# 1.net
KiCad netlist of a schematic drawn in Altium Designer
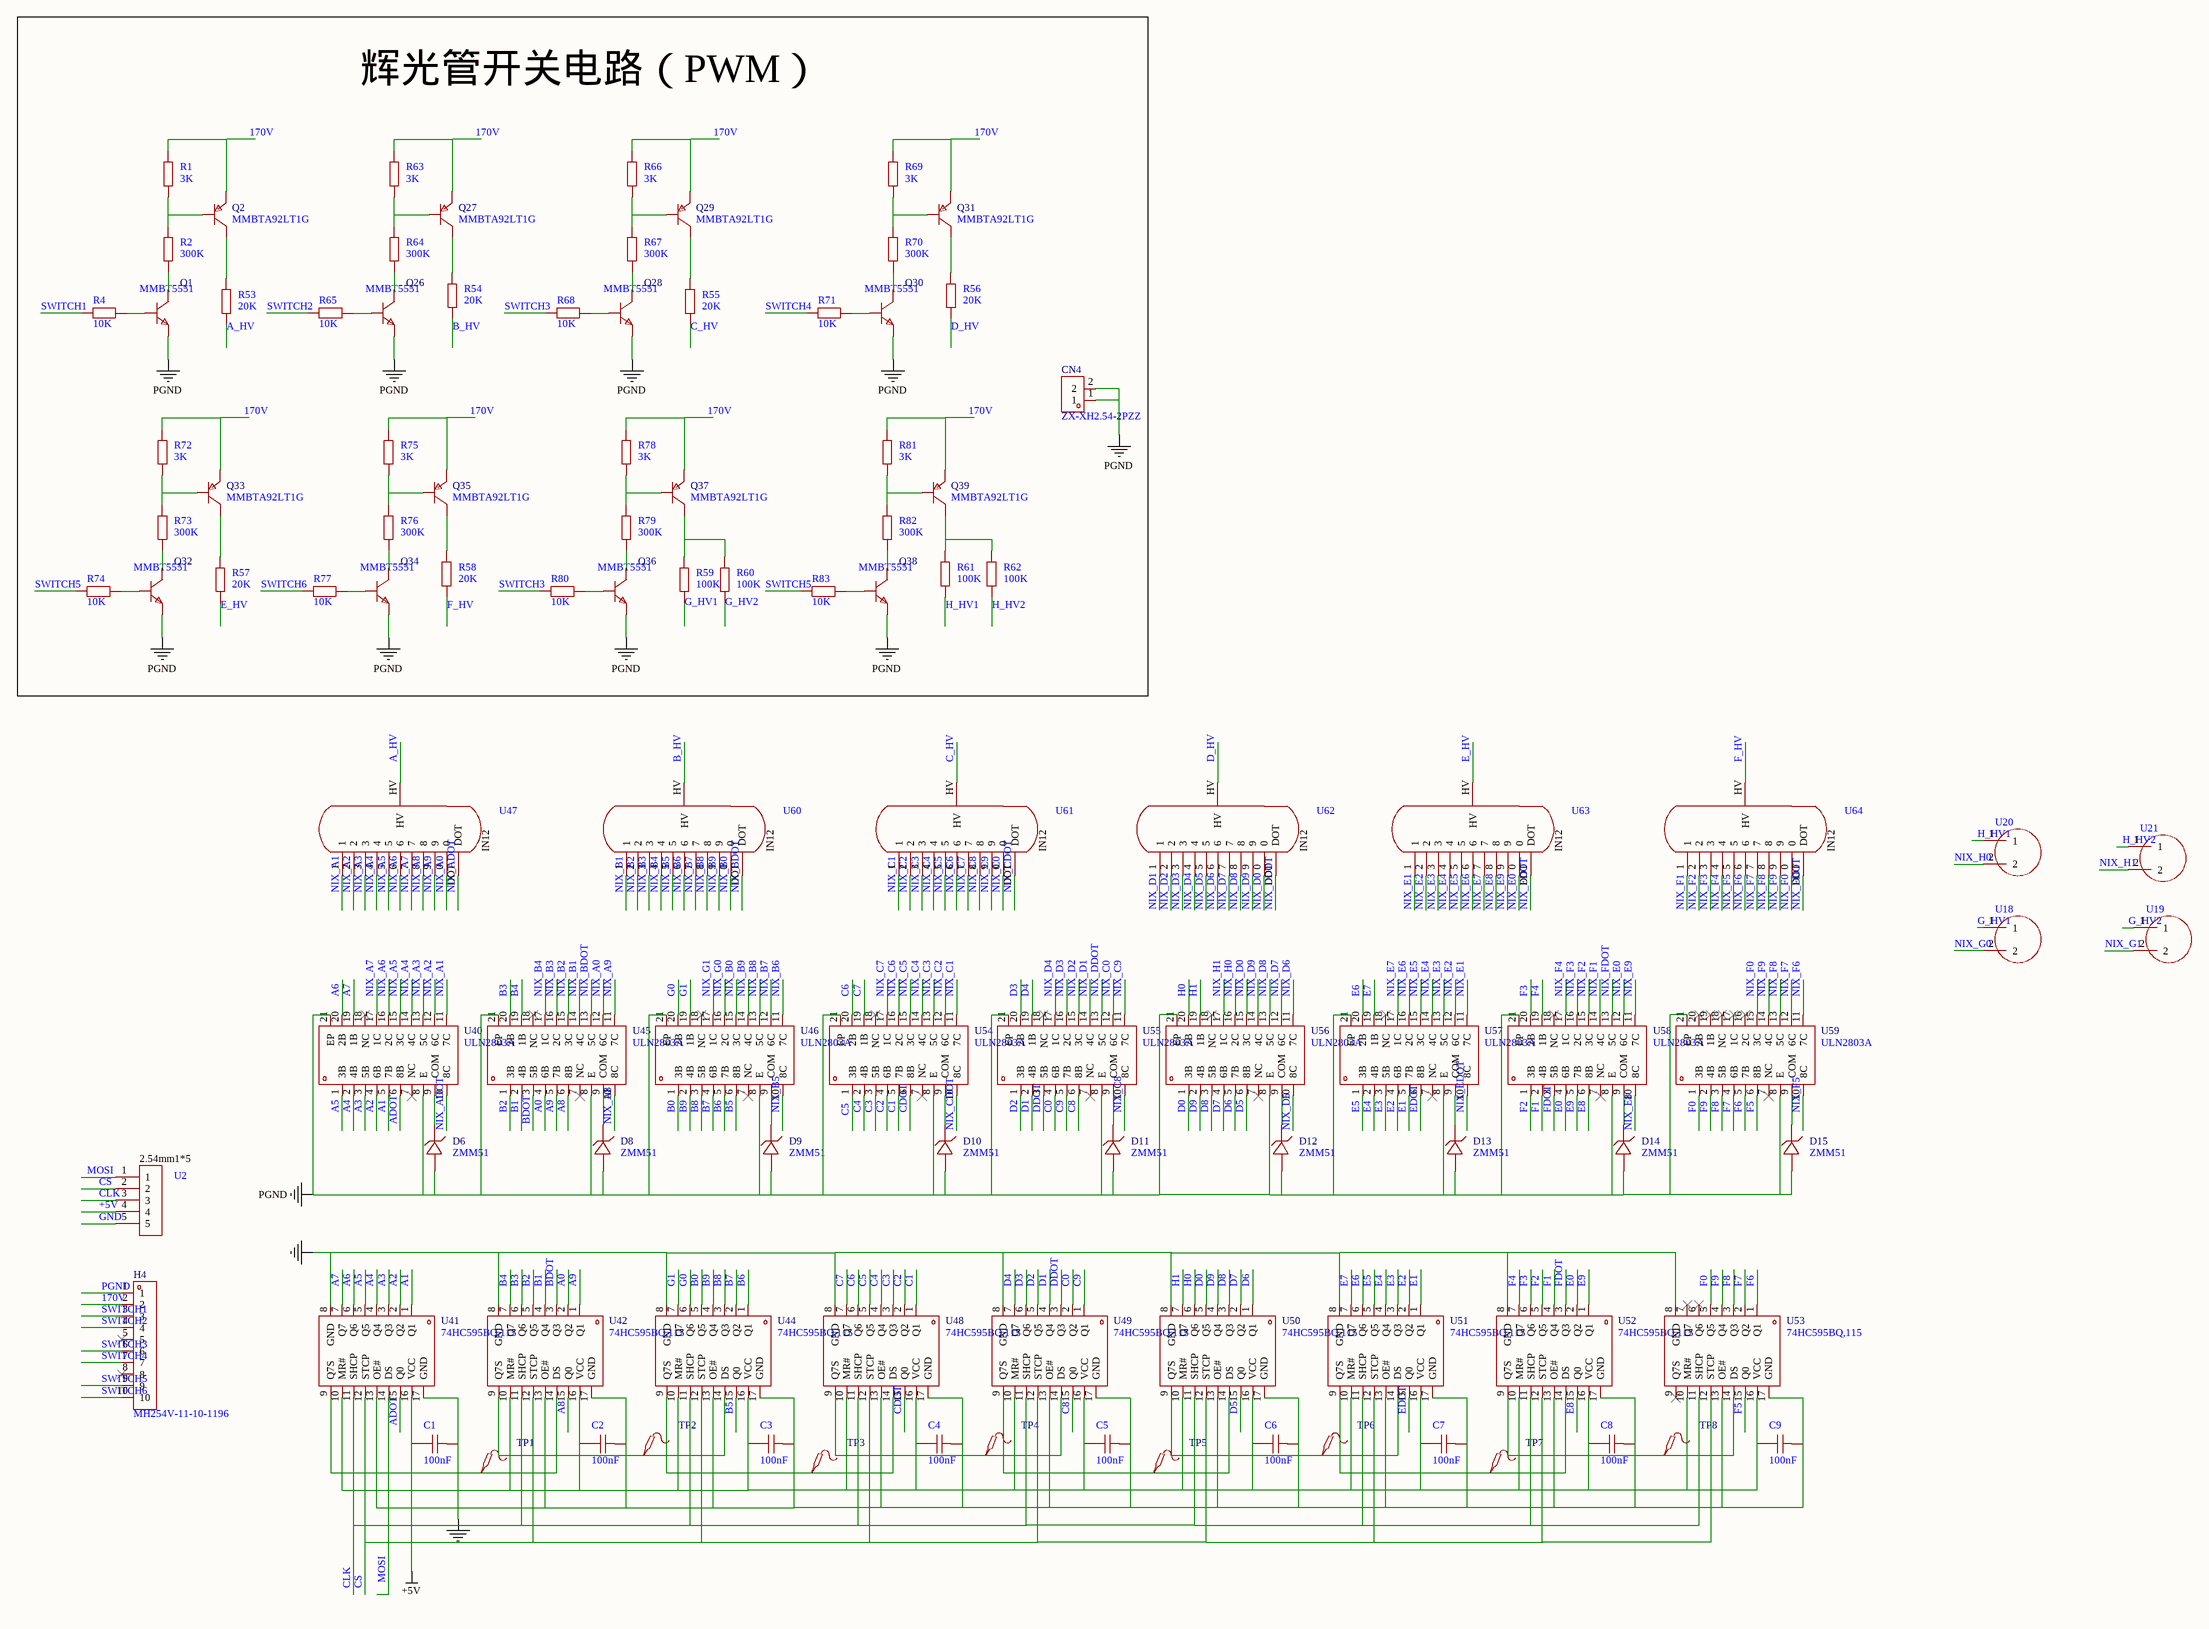
[diagram p0: 1_驱动.schdoc]

(export (version "E")
  (design (tool "Eeschema 10.0.6"))
  (components
    (comp (ref "C1")
      (value "100nF")
      (footprint "C0603")
      (libsource (lib "altium-import") (part "root_0_CAP_0603_"))
    )
    (comp (ref "C2")
      (value "100nF")
      (footprint "C0603")
      (libsource (lib "altium-import") (part "root_0_CAP_0603_"))
    )
    (comp (ref "C3")
      (value "100nF")
      (footprint "C0603")
      (libsource (lib "altium-import") (part "root_0_CAP_0603_"))
    )
    (comp (ref "C4")
      (value "100nF")
      (footprint "C0603")
      (libsource (lib "altium-import") (part "root_0_CAP_0603_"))
    )
    (comp (ref "C5")
      (value "100nF")
      (footprint "C0603")
      (libsource (lib "altium-import") (part "root_0_CAP_0603_"))
    )
    (comp (ref "C6")
      (value "100nF")
      (footprint "C0603")
      (libsource (lib "altium-import") (part "root_0_CAP_0603_"))
    )
    (comp (ref "C7")
      (value "100nF")
      (footprint "C0603")
      (libsource (lib "altium-import") (part "root_0_CAP_0603_"))
    )
    (comp (ref "C8")
      (value "100nF")
      (footprint "C0603")
      (libsource (lib "altium-import") (part "root_0_CAP_0603_"))
    )
    (comp (ref "C9")
      (value "100nF")
      (footprint "C0603")
      (libsource (lib "altium-import") (part "root_0_CAP_0603_"))
    )
    (comp (ref "CN4")
      (value "ZX-XH2.54-2PZZ")
      (footprint "CONN-TH_2P-P2.50_HX25003-2A")
      (fields (field (name "MANUFACTURER") "Megastar(兆星)"))
      (libsource (lib "altium-import") (part "root_2_ZX-XH2.54-2PZZ_"))
    )
    (comp (ref "D6")
      (value "ZMM51")
      (footprint "LL-34_L3.5-W1.5-RD")
      (fields (field (name "MANUFACTURER") "ST(先科)"))
      (libsource (lib "altium-import") (part "root_3_ZMM51_"))
    )
    (comp (ref "D8")
      (value "ZMM51")
      (footprint "LL-34_L3.5-W1.5-RD")
      (fields (field (name "MANUFACTURER") "ST(先科)"))
      (libsource (lib "altium-import") (part "root_3_ZMM51_"))
    )
    (comp (ref "D9")
      (value "ZMM51")
      (footprint "LL-34_L3.5-W1.5-RD")
      (fields (field (name "MANUFACTURER") "ST(先科)"))
      (libsource (lib "altium-import") (part "root_3_ZMM51_"))
    )
    (comp (ref "D10")
      (value "ZMM51")
      (footprint "LL-34_L3.5-W1.5-RD")
      (fields (field (name "MANUFACTURER") "ST(先科)"))
      (libsource (lib "altium-import") (part "root_3_ZMM51_"))
    )
    (comp (ref "D11")
      (value "ZMM51")
      (footprint "LL-34_L3.5-W1.5-RD")
      (fields (field (name "MANUFACTURER") "ST(先科)"))
      (libsource (lib "altium-import") (part "root_3_ZMM51_"))
    )
    (comp (ref "D12")
      (value "ZMM51")
      (footprint "LL-34_L3.5-W1.5-RD")
      (fields (field (name "MANUFACTURER") "ST(先科)"))
      (libsource (lib "altium-import") (part "root_3_ZMM51_"))
    )
    (comp (ref "D13")
      (value "ZMM51")
      (footprint "LL-34_L3.5-W1.5-RD")
      (fields (field (name "MANUFACTURER") "ST(先科)"))
      (libsource (lib "altium-import") (part "root_3_ZMM51_"))
    )
    (comp (ref "D14")
      (value "ZMM51")
      (footprint "LL-34_L3.5-W1.5-RD")
      (fields (field (name "MANUFACTURER") "ST(先科)"))
      (libsource (lib "altium-import") (part "root_3_ZMM51_"))
    )
    (comp (ref "D15")
      (value "ZMM51")
      (footprint "LL-34_L3.5-W1.5-RD")
      (fields (field (name "MANUFACTURER") "ST(先科)"))
      (libsource (lib "altium-import") (part "root_3_ZMM51_"))
    )
    (comp (ref "H4")
      (value "MH254V-11-10-1196")
      (footprint "HDR-TH_10P-P2.54-V-M")
      (fields (field (name "MANUFACTURER") "XFCN(兴飞)"))
      (libsource (lib "altium-import") (part "root_0_MH254V-11-10-1196_"))
    )
    (comp (ref "Q1")
      (value "MMBT5551")
      (footprint "SOT-23-3_L2.9-W1.3-P1.90-LS2.4-BR")
      (fields (field (name "MANUFACTURER") "CJ(江苏长电/长晶)"))
      (libsource (lib "altium-import") (part "root_0_MMBT5551_C2145_"))
    )
    (comp (ref "Q2")
      (value "MMBTA92LT1G")
      (footprint "SOT-23-3_L2.9-W1.6-P1.90-LS2.8-BR")
      (fields (field (name "MANUFACTURER") "onsemi(安森美)"))
      (libsource (lib "altium-import") (part "root_2_mirrored_MMBTA92LT1G_"))
    )
    (comp (ref "Q26")
      (value "MMBT5551")
      (footprint "SOT-23-3_L2.9-W1.3-P1.90-LS2.4-BR")
      (fields (field (name "MANUFACTURER") "CJ(江苏长电/长晶)"))
      (libsource (lib "altium-import") (part "root_0_MMBT5551_C2145_"))
    )
    (comp (ref "Q27")
      (value "MMBTA92LT1G")
      (footprint "SOT-23-3_L2.9-W1.6-P1.90-LS2.8-BR")
      (fields (field (name "MANUFACTURER") "onsemi(安森美)"))
      (libsource (lib "altium-import") (part "root_2_mirrored_MMBTA92LT1G_"))
    )
    (comp (ref "Q28")
      (value "MMBT5551")
      (footprint "SOT-23-3_L2.9-W1.3-P1.90-LS2.4-BR")
      (fields (field (name "MANUFACTURER") "CJ(江苏长电/长晶)"))
      (libsource (lib "altium-import") (part "root_0_MMBT5551_C2145_"))
    )
    (comp (ref "Q29")
      (value "MMBTA92LT1G")
      (footprint "SOT-23-3_L2.9-W1.6-P1.90-LS2.8-BR")
      (fields (field (name "MANUFACTURER") "onsemi(安森美)"))
      (libsource (lib "altium-import") (part "root_2_mirrored_MMBTA92LT1G_"))
    )
    (comp (ref "Q30")
      (value "MMBT5551")
      (footprint "SOT-23-3_L2.9-W1.3-P1.90-LS2.4-BR")
      (fields (field (name "MANUFACTURER") "CJ(江苏长电/长晶)"))
      (libsource (lib "altium-import") (part "root_0_MMBT5551_C2145_"))
    )
    (comp (ref "Q31")
      (value "MMBTA92LT1G")
      (footprint "SOT-23-3_L2.9-W1.6-P1.90-LS2.8-BR")
      (fields (field (name "MANUFACTURER") "onsemi(安森美)"))
      (libsource (lib "altium-import") (part "root_2_mirrored_MMBTA92LT1G_"))
    )
    (comp (ref "Q32")
      (value "MMBT5551")
      (footprint "SOT-23-3_L2.9-W1.3-P1.90-LS2.4-BR")
      (fields (field (name "MANUFACTURER") "CJ(江苏长电/长晶)"))
      (libsource (lib "altium-import") (part "root_0_MMBT5551_C2145_"))
    )
    (comp (ref "Q33")
      (value "MMBTA92LT1G")
      (footprint "SOT-23-3_L2.9-W1.6-P1.90-LS2.8-BR")
      (fields (field (name "MANUFACTURER") "onsemi(安森美)"))
      (libsource (lib "altium-import") (part "root_2_mirrored_MMBTA92LT1G_"))
    )
    (comp (ref "Q34")
      (value "MMBT5551")
      (footprint "SOT-23-3_L2.9-W1.3-P1.90-LS2.4-BR")
      (fields (field (name "MANUFACTURER") "CJ(江苏长电/长晶)"))
      (libsource (lib "altium-import") (part "root_0_MMBT5551_C2145_"))
    )
    (comp (ref "Q35")
      (value "MMBTA92LT1G")
      (footprint "SOT-23-3_L2.9-W1.6-P1.90-LS2.8-BR")
      (fields (field (name "MANUFACTURER") "onsemi(安森美)"))
      (libsource (lib "altium-import") (part "root_2_mirrored_MMBTA92LT1G_"))
    )
    (comp (ref "Q36")
      (value "MMBT5551")
      (footprint "SOT-23-3_L2.9-W1.3-P1.90-LS2.4-BR")
      (fields (field (name "MANUFACTURER") "CJ(江苏长电/长晶)"))
      (libsource (lib "altium-import") (part "root_0_MMBT5551_C2145_"))
    )
    (comp (ref "Q37")
      (value "MMBTA92LT1G")
      (footprint "SOT-23-3_L2.9-W1.6-P1.90-LS2.8-BR")
      (fields (field (name "MANUFACTURER") "onsemi(安森美)"))
      (libsource (lib "altium-import") (part "root_2_mirrored_MMBTA92LT1G_"))
    )
    (comp (ref "Q38")
      (value "MMBT5551")
      (footprint "SOT-23-3_L2.9-W1.3-P1.90-LS2.4-BR")
      (fields (field (name "MANUFACTURER") "CJ(江苏长电/长晶)"))
      (libsource (lib "altium-import") (part "root_0_MMBT5551_C2145_"))
    )
    (comp (ref "Q39")
      (value "MMBTA92LT1G")
      (footprint "SOT-23-3_L2.9-W1.6-P1.90-LS2.8-BR")
      (fields (field (name "MANUFACTURER") "onsemi(安森美)"))
      (libsource (lib "altium-import") (part "root_2_mirrored_MMBTA92LT1G_"))
    )
    (comp (ref "R1")
      (value "3K")
      (footprint "R0603")
      (libsource (lib "altium-import") (part "root_1_Res_0603_"))
    )
    (comp (ref "R2")
      (value "300K")
      (footprint "R0603")
      (libsource (lib "altium-import") (part "root_1_Res_0603_"))
    )
    (comp (ref "R4")
      (value "10K")
      (footprint "R0603")
      (libsource (lib "altium-import") (part "root_0_Res_0603_"))
    )
    (comp (ref "R53")
      (value "20K")
      (footprint "R0603")
      (libsource (lib "altium-import") (part "root_1_Res_0603_"))
    )
    (comp (ref "R54")
      (value "20K")
      (footprint "R0603")
      (libsource (lib "altium-import") (part "root_1_Res_0603_"))
    )
    (comp (ref "R55")
      (value "20K")
      (footprint "R0603")
      (libsource (lib "altium-import") (part "root_1_Res_0603_"))
    )
    (comp (ref "R56")
      (value "20K")
      (footprint "R0603")
      (libsource (lib "altium-import") (part "root_1_Res_0603_"))
    )
    (comp (ref "R57")
      (value "20K")
      (footprint "R0603")
      (libsource (lib "altium-import") (part "root_1_Res_0603_"))
    )
    (comp (ref "R58")
      (value "20K")
      (footprint "R0603")
      (libsource (lib "altium-import") (part "root_1_Res_0603_"))
    )
    (comp (ref "R59")
      (value "100K")
      (footprint "R0603")
      (libsource (lib "altium-import") (part "root_1_Res_0603_"))
    )
    (comp (ref "R60")
      (value "100K")
      (footprint "R0603")
      (libsource (lib "altium-import") (part "root_1_Res_0603_"))
    )
    (comp (ref "R61")
      (value "100K")
      (footprint "R0603")
      (libsource (lib "altium-import") (part "root_1_Res_0603_"))
    )
    (comp (ref "R62")
      (value "100K")
      (footprint "R0603")
      (libsource (lib "altium-import") (part "root_1_Res_0603_"))
    )
    (comp (ref "R63")
      (value "3K")
      (footprint "R0603")
      (libsource (lib "altium-import") (part "root_1_Res_0603_"))
    )
    (comp (ref "R64")
      (value "300K")
      (footprint "R0603")
      (libsource (lib "altium-import") (part "root_1_Res_0603_"))
    )
    (comp (ref "R65")
      (value "10K")
      (footprint "R0603")
      (libsource (lib "altium-import") (part "root_0_Res_0603_"))
    )
    (comp (ref "R66")
      (value "3K")
      (footprint "R0603")
      (libsource (lib "altium-import") (part "root_1_Res_0603_"))
    )
    (comp (ref "R67")
      (value "300K")
      (footprint "R0603")
      (libsource (lib "altium-import") (part "root_1_Res_0603_"))
    )
    (comp (ref "R68")
      (value "10K")
      (footprint "R0603")
      (libsource (lib "altium-import") (part "root_0_Res_0603_"))
    )
    (comp (ref "R69")
      (value "3K")
      (footprint "R0603")
      (libsource (lib "altium-import") (part "root_1_Res_0603_"))
    )
    (comp (ref "R70")
      (value "300K")
      (footprint "R0603")
      (libsource (lib "altium-import") (part "root_1_Res_0603_"))
    )
    (comp (ref "R71")
      (value "10K")
      (footprint "R0603")
      (libsource (lib "altium-import") (part "root_0_Res_0603_"))
    )
    (comp (ref "R72")
      (value "3K")
      (footprint "R0603")
      (libsource (lib "altium-import") (part "root_1_Res_0603_"))
    )
    (comp (ref "R73")
      (value "300K")
      (footprint "R0603")
      (libsource (lib "altium-import") (part "root_1_Res_0603_"))
    )
    (comp (ref "R74")
      (value "10K")
      (footprint "R0603")
      (libsource (lib "altium-import") (part "root_0_Res_0603_"))
    )
    (comp (ref "R75")
      (value "3K")
      (footprint "R0603")
      (libsource (lib "altium-import") (part "root_1_Res_0603_"))
    )
    (comp (ref "R76")
      (value "300K")
      (footprint "R0603")
      (libsource (lib "altium-import") (part "root_1_Res_0603_"))
    )
    (comp (ref "R77")
      (value "10K")
      (footprint "R0603")
      (libsource (lib "altium-import") (part "root_0_Res_0603_"))
    )
    (comp (ref "R78")
      (value "3K")
      (footprint "R0603")
      (libsource (lib "altium-import") (part "root_1_Res_0603_"))
    )
    (comp (ref "R79")
      (value "300K")
      (footprint "R0603")
      (libsource (lib "altium-import") (part "root_1_Res_0603_"))
    )
    (comp (ref "R80")
      (value "10K")
      (footprint "R0603")
      (libsource (lib "altium-import") (part "root_0_Res_0603_"))
    )
    (comp (ref "R81")
      (value "3K")
      (footprint "R0603")
      (libsource (lib "altium-import") (part "root_1_Res_0603_"))
    )
    (comp (ref "R82")
      (value "300K")
      (footprint "R0603")
      (libsource (lib "altium-import") (part "root_1_Res_0603_"))
    )
    (comp (ref "R83")
      (value "10K")
      (footprint "R0603")
      (libsource (lib "altium-import") (part "root_0_Res_0603_"))
    )
    (comp (ref "TP1")
      (value "~")
      (footprint "Test-Point-0.5mm")
      (libsource (lib "altium-import") (part "root_0_Test-Point_"))
    )
    (comp (ref "TP2")
      (value "~")
      (footprint "Test-Point-0.5mm")
      (libsource (lib "altium-import") (part "root_0_Test-Point_"))
    )
    (comp (ref "TP3")
      (value "~")
      (footprint "Test-Point-0.5mm")
      (libsource (lib "altium-import") (part "root_0_Test-Point_"))
    )
    (comp (ref "TP4")
      (value "~")
      (footprint "Test-Point-0.5mm")
      (libsource (lib "altium-import") (part "root_0_Test-Point_"))
    )
    (comp (ref "TP5")
      (value "~")
      (footprint "Test-Point-0.5mm")
      (libsource (lib "altium-import") (part "root_0_Test-Point_"))
    )
    (comp (ref "TP6")
      (value "~")
      (footprint "Test-Point-0.5mm")
      (libsource (lib "altium-import") (part "root_0_Test-Point_"))
    )
    (comp (ref "TP7")
      (value "~")
      (footprint "Test-Point-0.5mm")
      (libsource (lib "altium-import") (part "root_0_Test-Point_"))
    )
    (comp (ref "TP8")
      (value "~")
      (footprint "Test-Point-0.5mm")
      (libsource (lib "altium-import") (part "root_0_Test-Point_"))
    )
    (comp (ref "U2")
      (value "~")
      (footprint "2.54mm1*5")
      (libsource (lib "altium-import") (part "root_0_2.54mm1*5_"))
    )
    (comp (ref "U18") (value "~") (footprint "6*13氖泡") (libsource (lib "altium-import") (part "root_3_氖泡_")))
    (comp (ref "U19") (value "~") (footprint "6*13氖泡") (libsource (lib "altium-import") (part "root_3_氖泡_")))
    (comp (ref "U20") (value "~") (footprint "6*13氖泡") (libsource (lib "altium-import") (part "root_3_氖泡_")))
    (comp (ref "U21") (value "~") (footprint "6*13氖泡") (libsource (lib "altium-import") (part "root_3_氖泡_")))
    (comp (ref "U40")
      (value "ULN2803A")
      (footprint "QFN-20_L4.0-W4.0-P0.50-BL-EP")
      (fields (field (name "MANUFACTURER") "Mixic(中科芯亿达)"))
      (libsource (lib "altium-import") (part "root_1_ULN2803A_C493377_"))
    )
    (comp (ref "U41")
      (value "74HC595BQ,115")
      (footprint "DHVQFN-16_L3.5-W2.5-P0.50-BL-EP")
      (fields (field (name "MANUFACTURER") "Nexperia(安世)"))
      (libsource (lib "altium-import") (part "root_3_74HC595BQ,115_"))
    )
    (comp (ref "U42")
      (value "74HC595BQ,115")
      (footprint "DHVQFN-16_L3.5-W2.5-P0.50-BL-EP")
      (fields (field (name "MANUFACTURER") "Nexperia(安世)"))
      (libsource (lib "altium-import") (part "root_3_74HC595BQ,115_"))
    )
    (comp (ref "U44")
      (value "74HC595BQ,115")
      (footprint "DHVQFN-16_L3.5-W2.5-P0.50-BL-EP")
      (fields (field (name "MANUFACTURER") "Nexperia(安世)"))
      (libsource (lib "altium-import") (part "root_3_74HC595BQ,115_"))
    )
    (comp (ref "U45")
      (value "ULN2803A")
      (footprint "QFN-20_L4.0-W4.0-P0.50-BL-EP")
      (fields (field (name "MANUFACTURER") "Mixic(中科芯亿达)"))
      (libsource (lib "altium-import") (part "root_1_ULN2803A_C493377_"))
    )
    (comp (ref "U46")
      (value "ULN2803A")
      (footprint "QFN-20_L4.0-W4.0-P0.50-BL-EP")
      (fields (field (name "MANUFACTURER") "Mixic(中科芯亿达)"))
      (libsource (lib "altium-import") (part "root_1_ULN2803A_C493377_"))
    )
    (comp (ref "U47") (value "~") (footprint "IN12") (libsource (lib "altium-import") (part "root_1_IN12_")))
    (comp (ref "U48")
      (value "74HC595BQ,115")
      (footprint "DHVQFN-16_L3.5-W2.5-P0.50-BL-EP")
      (fields (field (name "MANUFACTURER") "Nexperia(安世)"))
      (libsource (lib "altium-import") (part "root_3_74HC595BQ,115_"))
    )
    (comp (ref "U49")
      (value "74HC595BQ,115")
      (footprint "DHVQFN-16_L3.5-W2.5-P0.50-BL-EP")
      (fields (field (name "MANUFACTURER") "Nexperia(安世)"))
      (libsource (lib "altium-import") (part "root_3_74HC595BQ,115_"))
    )
    (comp (ref "U50")
      (value "74HC595BQ,115")
      (footprint "DHVQFN-16_L3.5-W2.5-P0.50-BL-EP")
      (fields (field (name "MANUFACTURER") "Nexperia(安世)"))
      (libsource (lib "altium-import") (part "root_3_74HC595BQ,115_"))
    )
    (comp (ref "U51")
      (value "74HC595BQ,115")
      (footprint "DHVQFN-16_L3.5-W2.5-P0.50-BL-EP")
      (fields (field (name "MANUFACTURER") "Nexperia(安世)"))
      (libsource (lib "altium-import") (part "root_3_74HC595BQ,115_"))
    )
    (comp (ref "U52")
      (value "74HC595BQ,115")
      (footprint "DHVQFN-16_L3.5-W2.5-P0.50-BL-EP")
      (fields (field (name "MANUFACTURER") "Nexperia(安世)"))
      (libsource (lib "altium-import") (part "root_3_74HC595BQ,115_"))
    )
    (comp (ref "U53")
      (value "74HC595BQ,115")
      (footprint "DHVQFN-16_L3.5-W2.5-P0.50-BL-EP")
      (fields (field (name "MANUFACTURER") "Nexperia(安世)"))
      (libsource (lib "altium-import") (part "root_3_74HC595BQ,115_"))
    )
    (comp (ref "U54")
      (value "ULN2803A")
      (footprint "QFN-20_L4.0-W4.0-P0.50-BL-EP")
      (fields (field (name "MANUFACTURER") "Mixic(中科芯亿达)"))
      (libsource (lib "altium-import") (part "root_1_ULN2803A_C493377_"))
    )
    (comp (ref "U55")
      (value "ULN2803A")
      (footprint "QFN-20_L4.0-W4.0-P0.50-BL-EP")
      (fields (field (name "MANUFACTURER") "Mixic(中科芯亿达)"))
      (libsource (lib "altium-import") (part "root_1_ULN2803A_C493377_"))
    )
    (comp (ref "U56")
      (value "ULN2803A")
      (footprint "QFN-20_L4.0-W4.0-P0.50-BL-EP")
      (fields (field (name "MANUFACTURER") "Mixic(中科芯亿达)"))
      (libsource (lib "altium-import") (part "root_1_ULN2803A_C493377_"))
    )
    (comp (ref "U57")
      (value "ULN2803A")
      (footprint "QFN-20_L4.0-W4.0-P0.50-BL-EP")
      (fields (field (name "MANUFACTURER") "Mixic(中科芯亿达)"))
      (libsource (lib "altium-import") (part "root_1_ULN2803A_C493377_"))
    )
    (comp (ref "U58")
      (value "ULN2803A")
      (footprint "QFN-20_L4.0-W4.0-P0.50-BL-EP")
      (fields (field (name "MANUFACTURER") "Mixic(中科芯亿达)"))
      (libsource (lib "altium-import") (part "root_1_ULN2803A_C493377_"))
    )
    (comp (ref "U59")
      (value "ULN2803A")
      (footprint "QFN-20_L4.0-W4.0-P0.50-BL-EP")
      (fields (field (name "MANUFACTURER") "Mixic(中科芯亿达)"))
      (libsource (lib "altium-import") (part "root_1_ULN2803A_C493377_"))
    )
    (comp (ref "U60") (value "~") (footprint "IN12") (libsource (lib "altium-import") (part "root_1_IN12_")))
    (comp (ref "U61") (value "~") (footprint "IN12") (libsource (lib "altium-import") (part "root_1_IN12_")))
    (comp (ref "U62") (value "~") (footprint "IN12") (libsource (lib "altium-import") (part "root_1_IN12_")))
    (comp (ref "U63") (value "~") (footprint "IN12") (libsource (lib "altium-import") (part "root_1_IN12_")))
    (comp (ref "U64") (value "~") (footprint "IN12") (libsource (lib "altium-import") (part "root_1_IN12_")))
  )
  (nets
    (net (code "1") (name "+5V") (class "Default")
      (node (ref "C1") (pin "1") (pinfunction "1_1") (pintype "passive"))
      (node (ref "C2") (pin "1") (pinfunction "1_1") (pintype "passive"))
      (node (ref "C3") (pin "1") (pinfunction "1_1") (pintype "passive"))
      (node (ref "C4") (pin "1") (pinfunction "1_1") (pintype "passive"))
      (node (ref "C5") (pin "1") (pinfunction "1_1") (pintype "passive"))
      (node (ref "C6") (pin "1") (pinfunction "1_1") (pintype "passive"))
      (node (ref "C7") (pin "1") (pinfunction "1_1") (pintype "passive"))
      (node (ref "C8") (pin "1") (pinfunction "1_1") (pintype "passive"))
      (node (ref "C9") (pin "1") (pinfunction "1_1") (pintype "passive"))
      (node (ref "U2") (pin "4") (pinfunction "4_4") (pintype "passive"))
      (node (ref "U41") (pin "10") (pinfunction "MR#_10") (pintype "passive"))
      (node (ref "U41") (pin "16") (pinfunction "VCC_16") (pintype "passive"))
      (node (ref "U42") (pin "10") (pinfunction "MR#_10") (pintype "passive"))
      (node (ref "U42") (pin "16") (pinfunction "VCC_16") (pintype "passive"))
      (node (ref "U44") (pin "10") (pinfunction "MR#_10") (pintype "passive"))
      (node (ref "U44") (pin "16") (pinfunction "VCC_16") (pintype "passive"))
      (node (ref "U48") (pin "10") (pinfunction "MR#_10") (pintype "passive"))
      (node (ref "U48") (pin "16") (pinfunction "VCC_16") (pintype "passive"))
      (node (ref "U49") (pin "10") (pinfunction "MR#_10") (pintype "passive"))
      (node (ref "U49") (pin "16") (pinfunction "VCC_16") (pintype "passive"))
      (node (ref "U50") (pin "10") (pinfunction "MR#_10") (pintype "passive"))
      (node (ref "U50") (pin "16") (pinfunction "VCC_16") (pintype "passive"))
      (node (ref "U51") (pin "10") (pinfunction "MR#_10") (pintype "passive"))
      (node (ref "U51") (pin "16") (pinfunction "VCC_16") (pintype "passive"))
      (node (ref "U52") (pin "10") (pinfunction "MR#_10") (pintype "passive"))
      (node (ref "U52") (pin "16") (pinfunction "VCC_16") (pintype "passive"))
      (node (ref "U53") (pin "10") (pinfunction "MR#_10") (pintype "passive"))
      (node (ref "U53") (pin "16") (pinfunction "VCC_16") (pintype "passive"))
    )
    (net (code "2") (name "/170V") (class "Default")
      (node (ref "H4") (pin "2") (pinfunction "2_2") (pintype "passive"))
      (node (ref "Q2") (pin "2") (pinfunction "E_2") (pintype "passive"))
      (node (ref "Q27") (pin "2") (pinfunction "E_2") (pintype "passive"))
      (node (ref "Q29") (pin "2") (pinfunction "E_2") (pintype "passive"))
      (node (ref "Q31") (pin "2") (pinfunction "E_2") (pintype "passive"))
      (node (ref "Q33") (pin "2") (pinfunction "E_2") (pintype "passive"))
      (node (ref "Q35") (pin "2") (pinfunction "E_2") (pintype "passive"))
      (node (ref "Q37") (pin "2") (pinfunction "E_2") (pintype "passive"))
      (node (ref "Q39") (pin "2") (pinfunction "E_2") (pintype "passive"))
      (node (ref "R1") (pin "2") (pinfunction "2_2") (pintype "passive"))
      (node (ref "R63") (pin "2") (pinfunction "2_2") (pintype "passive"))
      (node (ref "R66") (pin "2") (pinfunction "2_2") (pintype "passive"))
      (node (ref "R69") (pin "2") (pinfunction "2_2") (pintype "passive"))
      (node (ref "R72") (pin "2") (pinfunction "2_2") (pintype "passive"))
      (node (ref "R75") (pin "2") (pinfunction "2_2") (pintype "passive"))
      (node (ref "R78") (pin "2") (pinfunction "2_2") (pintype "passive"))
      (node (ref "R81") (pin "2") (pinfunction "2_2") (pintype "passive"))
    )
    (net (code "3") (name "/A0") (class "Default")
      (node (ref "U42") (pin "2") (pinfunction "Q2_2") (pintype "passive"))
      (node (ref "U45") (pin "4") (pinfunction "6B_4") (pintype "passive"))
    )
    (net (code "4") (name "/A1") (class "Default")
      (node (ref "U40") (pin "5") (pinfunction "7B_5") (pintype "passive"))
      (node (ref "U41") (pin "1") (pinfunction "Q1_1") (pintype "passive"))
    )
    (net (code "5") (name "/A2") (class "Default")
      (node (ref "U40") (pin "4") (pinfunction "6B_4") (pintype "passive"))
      (node (ref "U41") (pin "2") (pinfunction "Q2_2") (pintype "passive"))
    )
    (net (code "6") (name "/A3") (class "Default")
      (node (ref "U40") (pin "3") (pinfunction "5B_3") (pintype "passive"))
      (node (ref "U41") (pin "3") (pinfunction "Q3_3") (pintype "passive"))
    )
    (net (code "7") (name "/A4") (class "Default")
      (node (ref "U40") (pin "2") (pinfunction "4B_2") (pintype "passive"))
      (node (ref "U41") (pin "4") (pinfunction "Q4_4") (pintype "passive"))
    )
    (net (code "8") (name "/A5") (class "Default")
      (node (ref "U40") (pin "1") (pinfunction "3B_1") (pintype "passive"))
      (node (ref "U41") (pin "5") (pinfunction "Q5_5") (pintype "passive"))
    )
    (net (code "9") (name "/A6") (class "Default")
      (node (ref "U40") (pin "20") (pinfunction "2B_20") (pintype "passive"))
      (node (ref "U41") (pin "6") (pinfunction "Q6_6") (pintype "passive"))
    )
    (net (code "10") (name "/A7") (class "Default")
      (node (ref "U40") (pin "19") (pinfunction "1B_19") (pintype "passive"))
      (node (ref "U41") (pin "7") (pinfunction "Q7_7") (pintype "passive"))
    )
    (net (code "11") (name "/A8") (class "Default")
      (node (ref "U42") (pin "15") (pinfunction "Q0_15") (pintype "passive"))
      (node (ref "U45") (pin "6") (pinfunction "8B_6") (pintype "passive"))
    )
    (net (code "12") (name "/A9") (class "Default")
      (node (ref "U42") (pin "1") (pinfunction "Q1_1") (pintype "passive"))
      (node (ref "U45") (pin "5") (pinfunction "7B_5") (pintype "passive"))
    )
    (net (code "13") (name "/ADOT") (class "Default")
      (node (ref "U40") (pin "6") (pinfunction "8B_6") (pintype "passive"))
      (node (ref "U41") (pin "15") (pinfunction "Q0_15") (pintype "passive"))
    )
    (net (code "14") (name "/A_HV") (class "Default")
      (node (ref "R53") (pin "1") (pinfunction "1_1") (pintype "passive"))
      (node (ref "U47") (pin "HV") (pinfunction "HV_HV") (pintype "passive"))
    )
    (net (code "15") (name "/B0") (class "Default")
      (node (ref "U44") (pin "5") (pinfunction "Q5_5") (pintype "passive"))
      (node (ref "U46") (pin "1") (pinfunction "3B_1") (pintype "passive"))
    )
    (net (code "16") (name "/B1") (class "Default")
      (node (ref "U42") (pin "4") (pinfunction "Q4_4") (pintype "passive"))
      (node (ref "U45") (pin "2") (pinfunction "4B_2") (pintype "passive"))
    )
    (net (code "17") (name "/B2") (class "Default")
      (node (ref "U42") (pin "5") (pinfunction "Q5_5") (pintype "passive"))
      (node (ref "U45") (pin "1") (pinfunction "3B_1") (pintype "passive"))
    )
    (net (code "18") (name "/B3") (class "Default")
      (node (ref "U42") (pin "6") (pinfunction "Q6_6") (pintype "passive"))
      (node (ref "U45") (pin "20") (pinfunction "2B_20") (pintype "passive"))
    )
    (net (code "19") (name "/B4") (class "Default")
      (node (ref "U42") (pin "7") (pinfunction "Q7_7") (pintype "passive"))
      (node (ref "U45") (pin "19") (pinfunction "1B_19") (pintype "passive"))
    )
    (net (code "20") (name "/B5") (class "Default")
      (node (ref "U44") (pin "15") (pinfunction "Q0_15") (pintype "passive"))
      (node (ref "U46") (pin "6") (pinfunction "8B_6") (pintype "passive"))
    )
    (net (code "21") (name "/B6") (class "Default")
      (node (ref "U44") (pin "1") (pinfunction "Q1_1") (pintype "passive"))
      (node (ref "U46") (pin "5") (pinfunction "7B_5") (pintype "passive"))
    )
    (net (code "22") (name "/B7") (class "Default")
      (node (ref "U44") (pin "2") (pinfunction "Q2_2") (pintype "passive"))
      (node (ref "U46") (pin "4") (pinfunction "6B_4") (pintype "passive"))
    )
    (net (code "23") (name "/B8") (class "Default")
      (node (ref "U44") (pin "3") (pinfunction "Q3_3") (pintype "passive"))
      (node (ref "U46") (pin "3") (pinfunction "5B_3") (pintype "passive"))
    )
    (net (code "24") (name "/B9") (class "Default")
      (node (ref "U44") (pin "4") (pinfunction "Q4_4") (pintype "passive"))
      (node (ref "U46") (pin "2") (pinfunction "4B_2") (pintype "passive"))
    )
    (net (code "25") (name "/BDOT") (class "Default")
      (node (ref "U42") (pin "3") (pinfunction "Q3_3") (pintype "passive"))
      (node (ref "U45") (pin "3") (pinfunction "5B_3") (pintype "passive"))
    )
    (net (code "26") (name "/B_HV") (class "Default")
      (node (ref "R54") (pin "1") (pinfunction "1_1") (pintype "passive"))
      (node (ref "U60") (pin "HV") (pinfunction "HV_HV") (pintype "passive"))
    )
    (net (code "27") (name "/C0") (class "Default")
      (node (ref "U49") (pin "2") (pinfunction "Q2_2") (pintype "passive"))
      (node (ref "U55") (pin "4") (pinfunction "6B_4") (pintype "passive"))
    )
    (net (code "28") (name "/C1") (class "Default")
      (node (ref "U48") (pin "1") (pinfunction "Q1_1") (pintype "passive"))
      (node (ref "U54") (pin "5") (pinfunction "7B_5") (pintype "passive"))
    )
    (net (code "29") (name "/C2") (class "Default")
      (node (ref "U48") (pin "2") (pinfunction "Q2_2") (pintype "passive"))
      (node (ref "U54") (pin "4") (pinfunction "6B_4") (pintype "passive"))
    )
    (net (code "30") (name "/C3") (class "Default")
      (node (ref "U48") (pin "3") (pinfunction "Q3_3") (pintype "passive"))
      (node (ref "U54") (pin "3") (pinfunction "5B_3") (pintype "passive"))
    )
    (net (code "31") (name "/C4") (class "Default")
      (node (ref "U48") (pin "4") (pinfunction "Q4_4") (pintype "passive"))
      (node (ref "U54") (pin "2") (pinfunction "4B_2") (pintype "passive"))
    )
    (net (code "32") (name "/C5") (class "Default")
      (node (ref "U48") (pin "5") (pinfunction "Q5_5") (pintype "passive"))
      (node (ref "U54") (pin "1") (pinfunction "3B_1") (pintype "passive"))
    )
    (net (code "33") (name "/C6") (class "Default")
      (node (ref "U48") (pin "6") (pinfunction "Q6_6") (pintype "passive"))
      (node (ref "U54") (pin "20") (pinfunction "2B_20") (pintype "passive"))
    )
    (net (code "34") (name "/C7") (class "Default")
      (node (ref "U48") (pin "7") (pinfunction "Q7_7") (pintype "passive"))
      (node (ref "U54") (pin "19") (pinfunction "1B_19") (pintype "passive"))
    )
    (net (code "35") (name "/C8") (class "Default")
      (node (ref "U49") (pin "15") (pinfunction "Q0_15") (pintype "passive"))
      (node (ref "U55") (pin "6") (pinfunction "8B_6") (pintype "passive"))
    )
    (net (code "36") (name "/C9") (class "Default")
      (node (ref "U49") (pin "1") (pinfunction "Q1_1") (pintype "passive"))
      (node (ref "U55") (pin "5") (pinfunction "7B_5") (pintype "passive"))
    )
    (net (code "37") (name "/CDOT") (class "Default")
      (node (ref "U48") (pin "15") (pinfunction "Q0_15") (pintype "passive"))
      (node (ref "U54") (pin "6") (pinfunction "8B_6") (pintype "passive"))
    )
    (net (code "38") (name "/CLK") (class "Default")
      (node (ref "U2") (pin "3") (pinfunction "3_3") (pintype "passive"))
      (node (ref "U41") (pin "11") (pinfunction "SHCP_11") (pintype "passive"))
      (node (ref "U42") (pin "11") (pinfunction "SHCP_11") (pintype "passive"))
      (node (ref "U44") (pin "11") (pinfunction "SHCP_11") (pintype "passive"))
      (node (ref "U48") (pin "11") (pinfunction "SHCP_11") (pintype "passive"))
      (node (ref "U49") (pin "11") (pinfunction "SHCP_11") (pintype "passive"))
      (node (ref "U50") (pin "11") (pinfunction "SHCP_11") (pintype "passive"))
      (node (ref "U51") (pin "11") (pinfunction "SHCP_11") (pintype "passive"))
      (node (ref "U52") (pin "11") (pinfunction "SHCP_11") (pintype "passive"))
      (node (ref "U53") (pin "11") (pinfunction "SHCP_11") (pintype "passive"))
    )
    (net (code "39") (name "/CS") (class "Default")
      (node (ref "U2") (pin "2") (pinfunction "2_2") (pintype "passive"))
      (node (ref "U41") (pin "12") (pinfunction "STCP_12") (pintype "passive"))
      (node (ref "U42") (pin "12") (pinfunction "STCP_12") (pintype "passive"))
      (node (ref "U44") (pin "12") (pinfunction "STCP_12") (pintype "passive"))
      (node (ref "U48") (pin "12") (pinfunction "STCP_12") (pintype "passive"))
      (node (ref "U49") (pin "12") (pinfunction "STCP_12") (pintype "passive"))
      (node (ref "U50") (pin "12") (pinfunction "STCP_12") (pintype "passive"))
      (node (ref "U51") (pin "12") (pinfunction "STCP_12") (pintype "passive"))
      (node (ref "U52") (pin "12") (pinfunction "STCP_12") (pintype "passive"))
      (node (ref "U53") (pin "12") (pinfunction "STCP_12") (pintype "passive"))
    )
    (net (code "40") (name "/C_HV") (class "Default")
      (node (ref "R55") (pin "1") (pinfunction "1_1") (pintype "passive"))
      (node (ref "U61") (pin "HV") (pinfunction "HV_HV") (pintype "passive"))
    )
    (net (code "41") (name "/D0") (class "Default")
      (node (ref "U50") (pin "5") (pinfunction "Q5_5") (pintype "passive"))
      (node (ref "U56") (pin "1") (pinfunction "3B_1") (pintype "passive"))
    )
    (net (code "42") (name "/D1") (class "Default")
      (node (ref "U49") (pin "4") (pinfunction "Q4_4") (pintype "passive"))
      (node (ref "U55") (pin "2") (pinfunction "4B_2") (pintype "passive"))
    )
    (net (code "43") (name "/D2") (class "Default")
      (node (ref "U49") (pin "5") (pinfunction "Q5_5") (pintype "passive"))
      (node (ref "U55") (pin "1") (pinfunction "3B_1") (pintype "passive"))
    )
    (net (code "44") (name "/D3") (class "Default")
      (node (ref "U49") (pin "6") (pinfunction "Q6_6") (pintype "passive"))
      (node (ref "U55") (pin "20") (pinfunction "2B_20") (pintype "passive"))
    )
    (net (code "45") (name "/D4") (class "Default")
      (node (ref "U49") (pin "7") (pinfunction "Q7_7") (pintype "passive"))
      (node (ref "U55") (pin "19") (pinfunction "1B_19") (pintype "passive"))
    )
    (net (code "46") (name "/D5") (class "Default")
      (node (ref "U50") (pin "15") (pinfunction "Q0_15") (pintype "passive"))
      (node (ref "U56") (pin "6") (pinfunction "8B_6") (pintype "passive"))
    )
    (net (code "47") (name "/D6") (class "Default")
      (node (ref "U50") (pin "1") (pinfunction "Q1_1") (pintype "passive"))
      (node (ref "U56") (pin "5") (pinfunction "7B_5") (pintype "passive"))
    )
    (net (code "48") (name "/D7") (class "Default")
      (node (ref "U50") (pin "2") (pinfunction "Q2_2") (pintype "passive"))
      (node (ref "U56") (pin "4") (pinfunction "6B_4") (pintype "passive"))
    )
    (net (code "49") (name "/D8") (class "Default")
      (node (ref "U50") (pin "3") (pinfunction "Q3_3") (pintype "passive"))
      (node (ref "U56") (pin "3") (pinfunction "5B_3") (pintype "passive"))
    )
    (net (code "50") (name "/D9") (class "Default")
      (node (ref "U50") (pin "4") (pinfunction "Q4_4") (pintype "passive"))
      (node (ref "U56") (pin "2") (pinfunction "4B_2") (pintype "passive"))
    )
    (net (code "51") (name "/DDOT") (class "Default")
      (node (ref "U49") (pin "3") (pinfunction "Q3_3") (pintype "passive"))
      (node (ref "U55") (pin "3") (pinfunction "5B_3") (pintype "passive"))
    )
    (net (code "52") (name "/D_HV") (class "Default")
      (node (ref "R56") (pin "1") (pinfunction "1_1") (pintype "passive"))
      (node (ref "U62") (pin "HV") (pinfunction "HV_HV") (pintype "passive"))
    )
    (net (code "53") (name "/E0") (class "Default")
      (node (ref "U52") (pin "2") (pinfunction "Q2_2") (pintype "passive"))
      (node (ref "U58") (pin "4") (pinfunction "6B_4") (pintype "passive"))
    )
    (net (code "54") (name "/E1") (class "Default")
      (node (ref "U51") (pin "1") (pinfunction "Q1_1") (pintype "passive"))
      (node (ref "U57") (pin "5") (pinfunction "7B_5") (pintype "passive"))
    )
    (net (code "55") (name "/E2") (class "Default")
      (node (ref "U51") (pin "2") (pinfunction "Q2_2") (pintype "passive"))
      (node (ref "U57") (pin "4") (pinfunction "6B_4") (pintype "passive"))
    )
    (net (code "56") (name "/E3") (class "Default")
      (node (ref "U51") (pin "3") (pinfunction "Q3_3") (pintype "passive"))
      (node (ref "U57") (pin "3") (pinfunction "5B_3") (pintype "passive"))
    )
    (net (code "57") (name "/E4") (class "Default")
      (node (ref "U51") (pin "4") (pinfunction "Q4_4") (pintype "passive"))
      (node (ref "U57") (pin "2") (pinfunction "4B_2") (pintype "passive"))
    )
    (net (code "58") (name "/E5") (class "Default")
      (node (ref "U51") (pin "5") (pinfunction "Q5_5") (pintype "passive"))
      (node (ref "U57") (pin "1") (pinfunction "3B_1") (pintype "passive"))
    )
    (net (code "59") (name "/E6") (class "Default")
      (node (ref "U51") (pin "6") (pinfunction "Q6_6") (pintype "passive"))
      (node (ref "U57") (pin "20") (pinfunction "2B_20") (pintype "passive"))
    )
    (net (code "60") (name "/E7") (class "Default")
      (node (ref "U51") (pin "7") (pinfunction "Q7_7") (pintype "passive"))
      (node (ref "U57") (pin "19") (pinfunction "1B_19") (pintype "passive"))
    )
    (net (code "61") (name "/E8") (class "Default")
      (node (ref "U52") (pin "15") (pinfunction "Q0_15") (pintype "passive"))
      (node (ref "U58") (pin "6") (pinfunction "8B_6") (pintype "passive"))
    )
    (net (code "62") (name "/E9") (class "Default")
      (node (ref "U52") (pin "1") (pinfunction "Q1_1") (pintype "passive"))
      (node (ref "U58") (pin "5") (pinfunction "7B_5") (pintype "passive"))
    )
    (net (code "63") (name "/EDOT") (class "Default")
      (node (ref "U51") (pin "15") (pinfunction "Q0_15") (pintype "passive"))
      (node (ref "U57") (pin "6") (pinfunction "8B_6") (pintype "passive"))
    )
    (net (code "64") (name "/E_HV") (class "Default")
      (node (ref "R57") (pin "1") (pinfunction "1_1") (pintype "passive"))
      (node (ref "U63") (pin "HV") (pinfunction "HV_HV") (pintype "passive"))
    )
    (net (code "65") (name "/F0") (class "Default")
      (node (ref "U53") (pin "5") (pinfunction "Q5_5") (pintype "passive"))
      (node (ref "U59") (pin "1") (pinfunction "3B_1") (pintype "passive"))
    )
    (net (code "66") (name "/F1") (class "Default")
      (node (ref "U52") (pin "4") (pinfunction "Q4_4") (pintype "passive"))
      (node (ref "U58") (pin "2") (pinfunction "4B_2") (pintype "passive"))
    )
    (net (code "67") (name "/F2") (class "Default")
      (node (ref "U52") (pin "5") (pinfunction "Q5_5") (pintype "passive"))
      (node (ref "U58") (pin "1") (pinfunction "3B_1") (pintype "passive"))
    )
    (net (code "68") (name "/F3") (class "Default")
      (node (ref "U52") (pin "6") (pinfunction "Q6_6") (pintype "passive"))
      (node (ref "U58") (pin "20") (pinfunction "2B_20") (pintype "passive"))
    )
    (net (code "69") (name "/F4") (class "Default")
      (node (ref "U52") (pin "7") (pinfunction "Q7_7") (pintype "passive"))
      (node (ref "U58") (pin "19") (pinfunction "1B_19") (pintype "passive"))
    )
    (net (code "70") (name "/F5") (class "Default")
      (node (ref "U53") (pin "15") (pinfunction "Q0_15") (pintype "passive"))
      (node (ref "U59") (pin "6") (pinfunction "8B_6") (pintype "passive"))
    )
    (net (code "71") (name "/F6") (class "Default")
      (node (ref "U53") (pin "1") (pinfunction "Q1_1") (pintype "passive"))
      (node (ref "U59") (pin "5") (pinfunction "7B_5") (pintype "passive"))
    )
    (net (code "72") (name "/F7") (class "Default")
      (node (ref "U53") (pin "2") (pinfunction "Q2_2") (pintype "passive"))
      (node (ref "U59") (pin "4") (pinfunction "6B_4") (pintype "passive"))
    )
    (net (code "73") (name "/F8") (class "Default")
      (node (ref "U53") (pin "3") (pinfunction "Q3_3") (pintype "passive"))
      (node (ref "U59") (pin "3") (pinfunction "5B_3") (pintype "passive"))
    )
    (net (code "74") (name "/F9") (class "Default")
      (node (ref "U53") (pin "4") (pinfunction "Q4_4") (pintype "passive"))
      (node (ref "U59") (pin "2") (pinfunction "4B_2") (pintype "passive"))
    )
    (net (code "75") (name "/FDOT") (class "Default")
      (node (ref "U52") (pin "3") (pinfunction "Q3_3") (pintype "passive"))
      (node (ref "U58") (pin "3") (pinfunction "5B_3") (pintype "passive"))
    )
    (net (code "76") (name "/F_HV") (class "Default")
      (node (ref "R58") (pin "1") (pinfunction "1_1") (pintype "passive"))
      (node (ref "U64") (pin "HV") (pinfunction "HV_HV") (pintype "passive"))
    )
    (net (code "77") (name "/G0") (class "Default")
      (node (ref "U44") (pin "6") (pinfunction "Q6_6") (pintype "passive"))
      (node (ref "U46") (pin "20") (pinfunction "2B_20") (pintype "passive"))
    )
    (net (code "78") (name "/G1") (class "Default")
      (node (ref "U44") (pin "7") (pinfunction "Q7_7") (pintype "passive"))
      (node (ref "U46") (pin "19") (pinfunction "1B_19") (pintype "passive"))
    )
    (net (code "79") (name "/G_HV1") (class "Default")
      (node (ref "R59") (pin "1") (pinfunction "1_1") (pintype "passive"))
      (node (ref "U18") (pin "1") (pinfunction "1_1") (pintype "passive"))
    )
    (net (code "80") (name "/G_HV2") (class "Default")
      (node (ref "R60") (pin "1") (pinfunction "1_1") (pintype "passive"))
      (node (ref "U19") (pin "1") (pinfunction "1_1") (pintype "passive"))
    )
    (net (code "81") (name "/H0") (class "Default")
      (node (ref "U50") (pin "6") (pinfunction "Q6_6") (pintype "passive"))
      (node (ref "U56") (pin "20") (pinfunction "2B_20") (pintype "passive"))
    )
    (net (code "82") (name "/H1") (class "Default")
      (node (ref "U50") (pin "7") (pinfunction "Q7_7") (pintype "passive"))
      (node (ref "U56") (pin "19") (pinfunction "1B_19") (pintype "passive"))
    )
    (net (code "83") (name "/H_HV1") (class "Default")
      (node (ref "R61") (pin "1") (pinfunction "1_1") (pintype "passive"))
      (node (ref "U20") (pin "1") (pinfunction "1_1") (pintype "passive"))
    )
    (net (code "84") (name "/H_HV2") (class "Default")
      (node (ref "R62") (pin "1") (pinfunction "1_1") (pintype "passive"))
      (node (ref "U21") (pin "1") (pinfunction "1_1") (pintype "passive"))
    )
    (net (code "85") (name "/MOSI") (class "Default")
      (node (ref "U2") (pin "1") (pinfunction "1_1") (pintype "passive"))
      (node (ref "U41") (pin "14") (pinfunction "DS_14") (pintype "passive"))
    )
    (net (code "86") (name "/NIX_A0") (class "Default")
      (node (ref "U45") (pin "12") (pinfunction "6C_12") (pintype "passive"))
      (node (ref "U47") (pin "0") (pinfunction "0_0") (pintype "passive"))
    )
    (net (code "87") (name "/NIX_A1") (class "Default")
      (node (ref "U40") (pin "11") (pinfunction "7C_11") (pintype "passive"))
      (node (ref "U47") (pin "1") (pinfunction "1_1") (pintype "passive"))
    )
    (net (code "88") (name "/NIX_A2") (class "Default")
      (node (ref "U40") (pin "12") (pinfunction "6C_12") (pintype "passive"))
      (node (ref "U47") (pin "2") (pinfunction "2_2") (pintype "passive"))
    )
    (net (code "89") (name "/NIX_A3") (class "Default")
      (node (ref "U40") (pin "13") (pinfunction "5C_13") (pintype "passive"))
      (node (ref "U47") (pin "3") (pinfunction "3_3") (pintype "passive"))
    )
    (net (code "90") (name "/NIX_A4") (class "Default")
      (node (ref "U40") (pin "14") (pinfunction "4C_14") (pintype "passive"))
      (node (ref "U47") (pin "4") (pinfunction "4_4") (pintype "passive"))
    )
    (net (code "91") (name "/NIX_A5") (class "Default")
      (node (ref "U40") (pin "15") (pinfunction "3C_15") (pintype "passive"))
      (node (ref "U47") (pin "5") (pinfunction "5_5") (pintype "passive"))
    )
    (net (code "92") (name "/NIX_A6") (class "Default")
      (node (ref "U40") (pin "16") (pinfunction "2C_16") (pintype "passive"))
      (node (ref "U47") (pin "6") (pinfunction "6_6") (pintype "passive"))
    )
    (net (code "93") (name "/NIX_A7") (class "Default")
      (node (ref "U40") (pin "17") (pinfunction "1C_17") (pintype "passive"))
      (node (ref "U47") (pin "7") (pinfunction "7_7") (pintype "passive"))
    )
    (net (code "94") (name "/NIX_A8") (class "Default")
      (node (ref "U45") (pin "10") (pinfunction "8C_10") (pintype "passive"))
      (node (ref "U47") (pin "8") (pinfunction "8_8") (pintype "passive"))
    )
    (net (code "95") (name "/NIX_A9") (class "Default")
      (node (ref "U45") (pin "11") (pinfunction "7C_11") (pintype "passive"))
      (node (ref "U47") (pin "9") (pinfunction "9_9") (pintype "passive"))
    )
    (net (code "96") (name "/NIX_ADOT") (class "Default")
      (node (ref "U40") (pin "10") (pinfunction "8C_10") (pintype "passive"))
      (node (ref "U47") (pin "DOT") (pinfunction "DOT_DOT") (pintype "passive"))
    )
    (net (code "97") (name "/NIX_B0") (class "Default")
      (node (ref "U46") (pin "15") (pinfunction "3C_15") (pintype "passive"))
      (node (ref "U60") (pin "0") (pinfunction "0_0") (pintype "passive"))
    )
    (net (code "98") (name "/NIX_B1") (class "Default")
      (node (ref "U45") (pin "14") (pinfunction "4C_14") (pintype "passive"))
      (node (ref "U60") (pin "1") (pinfunction "1_1") (pintype "passive"))
    )
    (net (code "99") (name "/NIX_B2") (class "Default")
      (node (ref "U45") (pin "15") (pinfunction "3C_15") (pintype "passive"))
      (node (ref "U60") (pin "2") (pinfunction "2_2") (pintype "passive"))
    )
    (net (code "100") (name "/NIX_B3") (class "Default")
      (node (ref "U45") (pin "16") (pinfunction "2C_16") (pintype "passive"))
      (node (ref "U60") (pin "3") (pinfunction "3_3") (pintype "passive"))
    )
    (net (code "101") (name "/NIX_B4") (class "Default")
      (node (ref "U45") (pin "17") (pinfunction "1C_17") (pintype "passive"))
      (node (ref "U60") (pin "4") (pinfunction "4_4") (pintype "passive"))
    )
    (net (code "102") (name "/NIX_B5") (class "Default")
      (node (ref "U46") (pin "10") (pinfunction "8C_10") (pintype "passive"))
      (node (ref "U60") (pin "5") (pinfunction "5_5") (pintype "passive"))
    )
    (net (code "103") (name "/NIX_B6") (class "Default")
      (node (ref "U46") (pin "11") (pinfunction "7C_11") (pintype "passive"))
      (node (ref "U60") (pin "6") (pinfunction "6_6") (pintype "passive"))
    )
    (net (code "104") (name "/NIX_B7") (class "Default")
      (node (ref "U46") (pin "12") (pinfunction "6C_12") (pintype "passive"))
      (node (ref "U60") (pin "7") (pinfunction "7_7") (pintype "passive"))
    )
    (net (code "105") (name "/NIX_B8") (class "Default")
      (node (ref "U46") (pin "13") (pinfunction "5C_13") (pintype "passive"))
      (node (ref "U60") (pin "8") (pinfunction "8_8") (pintype "passive"))
    )
    (net (code "106") (name "/NIX_B9") (class "Default")
      (node (ref "U46") (pin "14") (pinfunction "4C_14") (pintype "passive"))
      (node (ref "U60") (pin "9") (pinfunction "9_9") (pintype "passive"))
    )
    (net (code "107") (name "/NIX_BDOT") (class "Default")
      (node (ref "U45") (pin "13") (pinfunction "5C_13") (pintype "passive"))
      (node (ref "U60") (pin "DOT") (pinfunction "DOT_DOT") (pintype "passive"))
    )
    (net (code "108") (name "/NIX_C0") (class "Default")
      (node (ref "U55") (pin "12") (pinfunction "6C_12") (pintype "passive"))
      (node (ref "U61") (pin "0") (pinfunction "0_0") (pintype "passive"))
    )
    (net (code "109") (name "/NIX_C1") (class "Default")
      (node (ref "U54") (pin "11") (pinfunction "7C_11") (pintype "passive"))
      (node (ref "U61") (pin "1") (pinfunction "1_1") (pintype "passive"))
    )
    (net (code "110") (name "/NIX_C2") (class "Default")
      (node (ref "U54") (pin "12") (pinfunction "6C_12") (pintype "passive"))
      (node (ref "U61") (pin "2") (pinfunction "2_2") (pintype "passive"))
    )
    (net (code "111") (name "/NIX_C3") (class "Default")
      (node (ref "U54") (pin "13") (pinfunction "5C_13") (pintype "passive"))
      (node (ref "U61") (pin "3") (pinfunction "3_3") (pintype "passive"))
    )
    (net (code "112") (name "/NIX_C4") (class "Default")
      (node (ref "U54") (pin "14") (pinfunction "4C_14") (pintype "passive"))
      (node (ref "U61") (pin "4") (pinfunction "4_4") (pintype "passive"))
    )
    (net (code "113") (name "/NIX_C5") (class "Default")
      (node (ref "U54") (pin "15") (pinfunction "3C_15") (pintype "passive"))
      (node (ref "U61") (pin "5") (pinfunction "5_5") (pintype "passive"))
    )
    (net (code "114") (name "/NIX_C6") (class "Default")
      (node (ref "U54") (pin "16") (pinfunction "2C_16") (pintype "passive"))
      (node (ref "U61") (pin "6") (pinfunction "6_6") (pintype "passive"))
    )
    (net (code "115") (name "/NIX_C7") (class "Default")
      (node (ref "U54") (pin "17") (pinfunction "1C_17") (pintype "passive"))
      (node (ref "U61") (pin "7") (pinfunction "7_7") (pintype "passive"))
    )
    (net (code "116") (name "/NIX_C8") (class "Default")
      (node (ref "U55") (pin "10") (pinfunction "8C_10") (pintype "passive"))
      (node (ref "U61") (pin "8") (pinfunction "8_8") (pintype "passive"))
    )
    (net (code "117") (name "/NIX_C9") (class "Default")
      (node (ref "U55") (pin "11") (pinfunction "7C_11") (pintype "passive"))
      (node (ref "U61") (pin "9") (pinfunction "9_9") (pintype "passive"))
    )
    (net (code "118") (name "/NIX_CDOT") (class "Default")
      (node (ref "U54") (pin "10") (pinfunction "8C_10") (pintype "passive"))
      (node (ref "U61") (pin "DOT") (pinfunction "DOT_DOT") (pintype "passive"))
    )
    (net (code "119") (name "/NIX_D0") (class "Default")
      (node (ref "U56") (pin "15") (pinfunction "3C_15") (pintype "passive"))
      (node (ref "U62") (pin "0") (pinfunction "0_0") (pintype "passive"))
    )
    (net (code "120") (name "/NIX_D1") (class "Default")
      (node (ref "U55") (pin "14") (pinfunction "4C_14") (pintype "passive"))
      (node (ref "U62") (pin "1") (pinfunction "1_1") (pintype "passive"))
    )
    (net (code "121") (name "/NIX_D2") (class "Default")
      (node (ref "U55") (pin "15") (pinfunction "3C_15") (pintype "passive"))
      (node (ref "U62") (pin "2") (pinfunction "2_2") (pintype "passive"))
    )
    (net (code "122") (name "/NIX_D3") (class "Default")
      (node (ref "U55") (pin "16") (pinfunction "2C_16") (pintype "passive"))
      (node (ref "U62") (pin "3") (pinfunction "3_3") (pintype "passive"))
    )
    (net (code "123") (name "/NIX_D4") (class "Default")
      (node (ref "U55") (pin "17") (pinfunction "1C_17") (pintype "passive"))
      (node (ref "U62") (pin "4") (pinfunction "4_4") (pintype "passive"))
    )
    (net (code "124") (name "/NIX_D5") (class "Default")
      (node (ref "U56") (pin "10") (pinfunction "8C_10") (pintype "passive"))
      (node (ref "U62") (pin "5") (pinfunction "5_5") (pintype "passive"))
    )
    (net (code "125") (name "/NIX_D6") (class "Default")
      (node (ref "U56") (pin "11") (pinfunction "7C_11") (pintype "passive"))
      (node (ref "U62") (pin "6") (pinfunction "6_6") (pintype "passive"))
    )
    (net (code "126") (name "/NIX_D7") (class "Default")
      (node (ref "U56") (pin "12") (pinfunction "6C_12") (pintype "passive"))
      (node (ref "U62") (pin "7") (pinfunction "7_7") (pintype "passive"))
    )
    (net (code "127") (name "/NIX_D8") (class "Default")
      (node (ref "U56") (pin "13") (pinfunction "5C_13") (pintype "passive"))
      (node (ref "U62") (pin "8") (pinfunction "8_8") (pintype "passive"))
    )
    (net (code "128") (name "/NIX_D9") (class "Default")
      (node (ref "U56") (pin "14") (pinfunction "4C_14") (pintype "passive"))
      (node (ref "U62") (pin "9") (pinfunction "9_9") (pintype "passive"))
    )
    (net (code "129") (name "/NIX_DDOT") (class "Default")
      (node (ref "U55") (pin "13") (pinfunction "5C_13") (pintype "passive"))
      (node (ref "U62") (pin "DOT") (pinfunction "DOT_DOT") (pintype "passive"))
    )
    (net (code "130") (name "/NIX_E0") (class "Default")
      (node (ref "U58") (pin "12") (pinfunction "6C_12") (pintype "passive"))
      (node (ref "U63") (pin "0") (pinfunction "0_0") (pintype "passive"))
    )
    (net (code "131") (name "/NIX_E1") (class "Default")
      (node (ref "U57") (pin "11") (pinfunction "7C_11") (pintype "passive"))
      (node (ref "U63") (pin "1") (pinfunction "1_1") (pintype "passive"))
    )
    (net (code "132") (name "/NIX_E2") (class "Default")
      (node (ref "U57") (pin "12") (pinfunction "6C_12") (pintype "passive"))
      (node (ref "U63") (pin "2") (pinfunction "2_2") (pintype "passive"))
    )
    (net (code "133") (name "/NIX_E3") (class "Default")
      (node (ref "U57") (pin "13") (pinfunction "5C_13") (pintype "passive"))
      (node (ref "U63") (pin "3") (pinfunction "3_3") (pintype "passive"))
    )
    (net (code "134") (name "/NIX_E4") (class "Default")
      (node (ref "U57") (pin "14") (pinfunction "4C_14") (pintype "passive"))
      (node (ref "U63") (pin "4") (pinfunction "4_4") (pintype "passive"))
    )
    (net (code "135") (name "/NIX_E5") (class "Default")
      (node (ref "U57") (pin "15") (pinfunction "3C_15") (pintype "passive"))
      (node (ref "U63") (pin "5") (pinfunction "5_5") (pintype "passive"))
    )
    (net (code "136") (name "/NIX_E6") (class "Default")
      (node (ref "U57") (pin "16") (pinfunction "2C_16") (pintype "passive"))
      (node (ref "U63") (pin "6") (pinfunction "6_6") (pintype "passive"))
    )
    (net (code "137") (name "/NIX_E7") (class "Default")
      (node (ref "U57") (pin "17") (pinfunction "1C_17") (pintype "passive"))
      (node (ref "U63") (pin "7") (pinfunction "7_7") (pintype "passive"))
    )
    (net (code "138") (name "/NIX_E8") (class "Default")
      (node (ref "U58") (pin "10") (pinfunction "8C_10") (pintype "passive"))
      (node (ref "U63") (pin "8") (pinfunction "8_8") (pintype "passive"))
    )
    (net (code "139") (name "/NIX_E9") (class "Default")
      (node (ref "U58") (pin "11") (pinfunction "7C_11") (pintype "passive"))
      (node (ref "U63") (pin "9") (pinfunction "9_9") (pintype "passive"))
    )
    (net (code "140") (name "/NIX_EDOT") (class "Default")
      (node (ref "U57") (pin "10") (pinfunction "8C_10") (pintype "passive"))
      (node (ref "U63") (pin "DOT") (pinfunction "DOT_DOT") (pintype "passive"))
    )
    (net (code "141") (name "/NIX_F0") (class "Default")
      (node (ref "U59") (pin "15") (pinfunction "3C_15") (pintype "passive"))
      (node (ref "U64") (pin "0") (pinfunction "0_0") (pintype "passive"))
    )
    (net (code "142") (name "/NIX_F1") (class "Default")
      (node (ref "U58") (pin "14") (pinfunction "4C_14") (pintype "passive"))
      (node (ref "U64") (pin "1") (pinfunction "1_1") (pintype "passive"))
    )
    (net (code "143") (name "/NIX_F2") (class "Default")
      (node (ref "U58") (pin "15") (pinfunction "3C_15") (pintype "passive"))
      (node (ref "U64") (pin "2") (pinfunction "2_2") (pintype "passive"))
    )
    (net (code "144") (name "/NIX_F3") (class "Default")
      (node (ref "U58") (pin "16") (pinfunction "2C_16") (pintype "passive"))
      (node (ref "U64") (pin "3") (pinfunction "3_3") (pintype "passive"))
    )
    (net (code "145") (name "/NIX_F4") (class "Default")
      (node (ref "U58") (pin "17") (pinfunction "1C_17") (pintype "passive"))
      (node (ref "U64") (pin "4") (pinfunction "4_4") (pintype "passive"))
    )
    (net (code "146") (name "/NIX_F5") (class "Default")
      (node (ref "U59") (pin "10") (pinfunction "8C_10") (pintype "passive"))
      (node (ref "U64") (pin "5") (pinfunction "5_5") (pintype "passive"))
    )
    (net (code "147") (name "/NIX_F6") (class "Default")
      (node (ref "U59") (pin "11") (pinfunction "7C_11") (pintype "passive"))
      (node (ref "U64") (pin "6") (pinfunction "6_6") (pintype "passive"))
    )
    (net (code "148") (name "/NIX_F7") (class "Default")
      (node (ref "U59") (pin "12") (pinfunction "6C_12") (pintype "passive"))
      (node (ref "U64") (pin "7") (pinfunction "7_7") (pintype "passive"))
    )
    (net (code "149") (name "/NIX_F8") (class "Default")
      (node (ref "U59") (pin "13") (pinfunction "5C_13") (pintype "passive"))
      (node (ref "U64") (pin "8") (pinfunction "8_8") (pintype "passive"))
    )
    (net (code "150") (name "/NIX_F9") (class "Default")
      (node (ref "U59") (pin "14") (pinfunction "4C_14") (pintype "passive"))
      (node (ref "U64") (pin "9") (pinfunction "9_9") (pintype "passive"))
    )
    (net (code "151") (name "/NIX_FDOT") (class "Default")
      (node (ref "U58") (pin "13") (pinfunction "5C_13") (pintype "passive"))
      (node (ref "U64") (pin "DOT") (pinfunction "DOT_DOT") (pintype "passive"))
    )
    (net (code "152") (name "/NIX_G0") (class "Default")
      (node (ref "U18") (pin "2") (pinfunction "2_2") (pintype "passive"))
      (node (ref "U46") (pin "16") (pinfunction "2C_16") (pintype "passive"))
    )
    (net (code "153") (name "/NIX_G1") (class "Default")
      (node (ref "U19") (pin "2") (pinfunction "2_2") (pintype "passive"))
      (node (ref "U46") (pin "17") (pinfunction "1C_17") (pintype "passive"))
    )
    (net (code "154") (name "/NIX_H0") (class "Default")
      (node (ref "U20") (pin "2") (pinfunction "2_2") (pintype "passive"))
      (node (ref "U56") (pin "16") (pinfunction "2C_16") (pintype "passive"))
    )
    (net (code "155") (name "/NIX_H1") (class "Default")
      (node (ref "U21") (pin "2") (pinfunction "2_2") (pintype "passive"))
      (node (ref "U56") (pin "17") (pinfunction "1C_17") (pintype "passive"))
    )
    (net (code "156") (name "/SWITCH1") (class "Default")
      (node (ref "H4") (pin "3") (pinfunction "3_3") (pintype "passive"))
      (node (ref "R4") (pin "1") (pinfunction "1_1") (pintype "passive"))
    )
    (net (code "157") (name "/SWITCH2") (class "Default")
      (node (ref "H4") (pin "4") (pinfunction "4_4") (pintype "passive"))
      (node (ref "R65") (pin "1") (pinfunction "1_1") (pintype "passive"))
    )
    (net (code "158") (name "/SWITCH3") (class "Default")
      (node (ref "H4") (pin "6") (pinfunction "6_6") (pintype "passive"))
      (node (ref "R68") (pin "1") (pinfunction "1_1") (pintype "passive"))
      (node (ref "R80") (pin "1") (pinfunction "1_1") (pintype "passive"))
    )
    (net (code "159") (name "/SWITCH4") (class "Default")
      (node (ref "H4") (pin "7") (pinfunction "7_7") (pintype "passive"))
      (node (ref "R71") (pin "1") (pinfunction "1_1") (pintype "passive"))
    )
    (net (code "160") (name "/SWITCH5") (class "Default")
      (node (ref "H4") (pin "9") (pinfunction "9_9") (pintype "passive"))
      (node (ref "R74") (pin "1") (pinfunction "1_1") (pintype "passive"))
      (node (ref "R83") (pin "1") (pinfunction "1_1") (pintype "passive"))
    )
    (net (code "161") (name "/SWITCH6") (class "Default")
      (node (ref "H4") (pin "10") (pinfunction "10_10") (pintype "passive"))
      (node (ref "R77") (pin "1") (pinfunction "1_1") (pintype "passive"))
    )
    (net (code "162") (name "GND") (class "Default")
      (node (ref "C1") (pin "2") (pinfunction "2_2") (pintype "passive"))
      (node (ref "C2") (pin "2") (pinfunction "2_2") (pintype "passive"))
      (node (ref "C3") (pin "2") (pinfunction "2_2") (pintype "passive"))
      (node (ref "C4") (pin "2") (pinfunction "2_2") (pintype "passive"))
      (node (ref "C5") (pin "2") (pinfunction "2_2") (pintype "passive"))
      (node (ref "C6") (pin "2") (pinfunction "2_2") (pintype "passive"))
      (node (ref "C7") (pin "2") (pinfunction "2_2") (pintype "passive"))
      (node (ref "C8") (pin "2") (pinfunction "2_2") (pintype "passive"))
      (node (ref "C9") (pin "2") (pinfunction "2_2") (pintype "passive"))
      (node (ref "U2") (pin "5") (pinfunction "5_5") (pintype "passive"))
      (node (ref "U41") (pin "13") (pinfunction "OE#_13") (pintype "passive"))
      (node (ref "U41") (pin "17") (pinfunction "GND_17") (pintype "passive"))
      (node (ref "U41") (pin "8") (pinfunction "GND_8") (pintype "passive"))
      (node (ref "U42") (pin "13") (pinfunction "OE#_13") (pintype "passive"))
      (node (ref "U42") (pin "17") (pinfunction "GND_17") (pintype "passive"))
      (node (ref "U42") (pin "8") (pinfunction "GND_8") (pintype "passive"))
      (node (ref "U44") (pin "13") (pinfunction "OE#_13") (pintype "passive"))
      (node (ref "U44") (pin "17") (pinfunction "GND_17") (pintype "passive"))
      (node (ref "U44") (pin "8") (pinfunction "GND_8") (pintype "passive"))
      (node (ref "U48") (pin "13") (pinfunction "OE#_13") (pintype "passive"))
      (node (ref "U48") (pin "17") (pinfunction "GND_17") (pintype "passive"))
      (node (ref "U48") (pin "8") (pinfunction "GND_8") (pintype "passive"))
      (node (ref "U49") (pin "13") (pinfunction "OE#_13") (pintype "passive"))
      (node (ref "U49") (pin "17") (pinfunction "GND_17") (pintype "passive"))
      (node (ref "U49") (pin "8") (pinfunction "GND_8") (pintype "passive"))
      (node (ref "U50") (pin "13") (pinfunction "OE#_13") (pintype "passive"))
      (node (ref "U50") (pin "17") (pinfunction "GND_17") (pintype "passive"))
      (node (ref "U50") (pin "8") (pinfunction "GND_8") (pintype "passive"))
      (node (ref "U51") (pin "13") (pinfunction "OE#_13") (pintype "passive"))
      (node (ref "U51") (pin "17") (pinfunction "GND_17") (pintype "passive"))
      (node (ref "U51") (pin "8") (pinfunction "GND_8") (pintype "passive"))
      (node (ref "U52") (pin "13") (pinfunction "OE#_13") (pintype "passive"))
      (node (ref "U52") (pin "17") (pinfunction "GND_17") (pintype "passive"))
      (node (ref "U52") (pin "8") (pinfunction "GND_8") (pintype "passive"))
      (node (ref "U53") (pin "13") (pinfunction "OE#_13") (pintype "passive"))
      (node (ref "U53") (pin "17") (pinfunction "GND_17") (pintype "passive"))
      (node (ref "U53") (pin "8") (pinfunction "GND_8") (pintype "passive"))
    )
    (net (code "163") (name "Net-(D6-C)") (class "Default")
      (node (ref "D6") (pin "1") (pinfunction "C_1") (pintype "passive"))
      (node (ref "U40") (pin "9") (pinfunction "COM_9") (pintype "passive"))
    )
    (net (code "164") (name "Net-(D8-C)") (class "Default")
      (node (ref "D8") (pin "1") (pinfunction "C_1") (pintype "passive"))
      (node (ref "U45") (pin "9") (pinfunction "COM_9") (pintype "passive"))
    )
    (net (code "165") (name "Net-(D9-C)") (class "Default")
      (node (ref "D9") (pin "1") (pinfunction "C_1") (pintype "passive"))
      (node (ref "U46") (pin "9") (pinfunction "COM_9") (pintype "passive"))
    )
    (net (code "166") (name "Net-(D10-C)") (class "Default")
      (node (ref "D10") (pin "1") (pinfunction "C_1") (pintype "passive"))
      (node (ref "U54") (pin "9") (pinfunction "COM_9") (pintype "passive"))
    )
    (net (code "167") (name "Net-(D11-C)") (class "Default")
      (node (ref "D11") (pin "1") (pinfunction "C_1") (pintype "passive"))
      (node (ref "U55") (pin "9") (pinfunction "COM_9") (pintype "passive"))
    )
    (net (code "168") (name "Net-(D12-C)") (class "Default")
      (node (ref "D12") (pin "1") (pinfunction "C_1") (pintype "passive"))
      (node (ref "U56") (pin "9") (pinfunction "COM_9") (pintype "passive"))
    )
    (net (code "169") (name "Net-(D13-C)") (class "Default")
      (node (ref "D13") (pin "1") (pinfunction "C_1") (pintype "passive"))
      (node (ref "U57") (pin "9") (pinfunction "COM_9") (pintype "passive"))
    )
    (net (code "170") (name "Net-(D14-C)") (class "Default")
      (node (ref "D14") (pin "1") (pinfunction "C_1") (pintype "passive"))
      (node (ref "U58") (pin "9") (pinfunction "COM_9") (pintype "passive"))
    )
    (net (code "171") (name "Net-(D15-C)") (class "Default")
      (node (ref "D15") (pin "1") (pinfunction "C_1") (pintype "passive"))
      (node (ref "U59") (pin "9") (pinfunction "COM_9") (pintype "passive"))
    )
    (net (code "172") (name "Net-(Q1-B)") (class "Default")
      (node (ref "Q1") (pin "1") (pinfunction "B_1") (pintype "passive"))
      (node (ref "R4") (pin "2") (pinfunction "2_2") (pintype "passive"))
    )
    (net (code "173") (name "Net-(Q1-C)") (class "Default")
      (node (ref "Q1") (pin "3") (pinfunction "C_3") (pintype "passive"))
      (node (ref "R2") (pin "1") (pinfunction "1_1") (pintype "passive"))
    )
    (net (code "174") (name "Net-(Q2-B)") (class "Default")
      (node (ref "Q2") (pin "1") (pinfunction "B_1") (pintype "passive"))
      (node (ref "R1") (pin "1") (pinfunction "1_1") (pintype "passive"))
      (node (ref "R2") (pin "2") (pinfunction "2_2") (pintype "passive"))
    )
    (net (code "175") (name "Net-(Q2-C)") (class "Default")
      (node (ref "Q2") (pin "3") (pinfunction "C_3") (pintype "passive"))
      (node (ref "R53") (pin "2") (pinfunction "2_2") (pintype "passive"))
    )
    (net (code "176") (name "Net-(Q26-B)") (class "Default")
      (node (ref "Q26") (pin "1") (pinfunction "B_1") (pintype "passive"))
      (node (ref "R65") (pin "2") (pinfunction "2_2") (pintype "passive"))
    )
    (net (code "177") (name "Net-(Q26-C)") (class "Default")
      (node (ref "Q26") (pin "3") (pinfunction "C_3") (pintype "passive"))
      (node (ref "R64") (pin "1") (pinfunction "1_1") (pintype "passive"))
    )
    (net (code "178") (name "Net-(Q27-B)") (class "Default")
      (node (ref "Q27") (pin "1") (pinfunction "B_1") (pintype "passive"))
      (node (ref "R63") (pin "1") (pinfunction "1_1") (pintype "passive"))
      (node (ref "R64") (pin "2") (pinfunction "2_2") (pintype "passive"))
    )
    (net (code "179") (name "Net-(Q27-C)") (class "Default")
      (node (ref "Q27") (pin "3") (pinfunction "C_3") (pintype "passive"))
      (node (ref "R54") (pin "2") (pinfunction "2_2") (pintype "passive"))
    )
    (net (code "180") (name "Net-(Q28-B)") (class "Default")
      (node (ref "Q28") (pin "1") (pinfunction "B_1") (pintype "passive"))
      (node (ref "R68") (pin "2") (pinfunction "2_2") (pintype "passive"))
    )
    (net (code "181") (name "Net-(Q28-C)") (class "Default")
      (node (ref "Q28") (pin "3") (pinfunction "C_3") (pintype "passive"))
      (node (ref "R67") (pin "1") (pinfunction "1_1") (pintype "passive"))
    )
    (net (code "182") (name "Net-(Q29-B)") (class "Default")
      (node (ref "Q29") (pin "1") (pinfunction "B_1") (pintype "passive"))
      (node (ref "R66") (pin "1") (pinfunction "1_1") (pintype "passive"))
      (node (ref "R67") (pin "2") (pinfunction "2_2") (pintype "passive"))
    )
    (net (code "183") (name "Net-(Q29-C)") (class "Default")
      (node (ref "Q29") (pin "3") (pinfunction "C_3") (pintype "passive"))
      (node (ref "R55") (pin "2") (pinfunction "2_2") (pintype "passive"))
    )
    (net (code "184") (name "Net-(Q30-B)") (class "Default")
      (node (ref "Q30") (pin "1") (pinfunction "B_1") (pintype "passive"))
      (node (ref "R71") (pin "2") (pinfunction "2_2") (pintype "passive"))
    )
    (net (code "185") (name "Net-(Q30-C)") (class "Default")
      (node (ref "Q30") (pin "3") (pinfunction "C_3") (pintype "passive"))
      (node (ref "R70") (pin "1") (pinfunction "1_1") (pintype "passive"))
    )
    (net (code "186") (name "Net-(Q31-B)") (class "Default")
      (node (ref "Q31") (pin "1") (pinfunction "B_1") (pintype "passive"))
      (node (ref "R69") (pin "1") (pinfunction "1_1") (pintype "passive"))
      (node (ref "R70") (pin "2") (pinfunction "2_2") (pintype "passive"))
    )
    (net (code "187") (name "Net-(Q31-C)") (class "Default")
      (node (ref "Q31") (pin "3") (pinfunction "C_3") (pintype "passive"))
      (node (ref "R56") (pin "2") (pinfunction "2_2") (pintype "passive"))
    )
    (net (code "188") (name "Net-(Q32-B)") (class "Default")
      (node (ref "Q32") (pin "1") (pinfunction "B_1") (pintype "passive"))
      (node (ref "R74") (pin "2") (pinfunction "2_2") (pintype "passive"))
    )
    (net (code "189") (name "Net-(Q32-C)") (class "Default")
      (node (ref "Q32") (pin "3") (pinfunction "C_3") (pintype "passive"))
      (node (ref "R73") (pin "1") (pinfunction "1_1") (pintype "passive"))
    )
    (net (code "190") (name "Net-(Q33-B)") (class "Default")
      (node (ref "Q33") (pin "1") (pinfunction "B_1") (pintype "passive"))
      (node (ref "R72") (pin "1") (pinfunction "1_1") (pintype "passive"))
      (node (ref "R73") (pin "2") (pinfunction "2_2") (pintype "passive"))
    )
    (net (code "191") (name "Net-(Q33-C)") (class "Default")
      (node (ref "Q33") (pin "3") (pinfunction "C_3") (pintype "passive"))
      (node (ref "R57") (pin "2") (pinfunction "2_2") (pintype "passive"))
    )
    (net (code "192") (name "Net-(Q34-B)") (class "Default")
      (node (ref "Q34") (pin "1") (pinfunction "B_1") (pintype "passive"))
      (node (ref "R77") (pin "2") (pinfunction "2_2") (pintype "passive"))
    )
    (net (code "193") (name "Net-(Q34-C)") (class "Default")
      (node (ref "Q34") (pin "3") (pinfunction "C_3") (pintype "passive"))
      (node (ref "R76") (pin "1") (pinfunction "1_1") (pintype "passive"))
    )
    (net (code "194") (name "Net-(Q35-B)") (class "Default")
      (node (ref "Q35") (pin "1") (pinfunction "B_1") (pintype "passive"))
      (node (ref "R75") (pin "1") (pinfunction "1_1") (pintype "passive"))
      (node (ref "R76") (pin "2") (pinfunction "2_2") (pintype "passive"))
    )
    (net (code "195") (name "Net-(Q35-C)") (class "Default")
      (node (ref "Q35") (pin "3") (pinfunction "C_3") (pintype "passive"))
      (node (ref "R58") (pin "2") (pinfunction "2_2") (pintype "passive"))
    )
    (net (code "196") (name "Net-(Q36-B)") (class "Default")
      (node (ref "Q36") (pin "1") (pinfunction "B_1") (pintype "passive"))
      (node (ref "R80") (pin "2") (pinfunction "2_2") (pintype "passive"))
    )
    (net (code "197") (name "Net-(Q36-C)") (class "Default")
      (node (ref "Q36") (pin "3") (pinfunction "C_3") (pintype "passive"))
      (node (ref "R79") (pin "1") (pinfunction "1_1") (pintype "passive"))
    )
    (net (code "198") (name "Net-(Q37-B)") (class "Default")
      (node (ref "Q37") (pin "1") (pinfunction "B_1") (pintype "passive"))
      (node (ref "R78") (pin "1") (pinfunction "1_1") (pintype "passive"))
      (node (ref "R79") (pin "2") (pinfunction "2_2") (pintype "passive"))
    )
    (net (code "199") (name "Net-(Q37-C)") (class "Default")
      (node (ref "Q37") (pin "3") (pinfunction "C_3") (pintype "passive"))
      (node (ref "R59") (pin "2") (pinfunction "2_2") (pintype "passive"))
      (node (ref "R60") (pin "2") (pinfunction "2_2") (pintype "passive"))
    )
    (net (code "200") (name "Net-(Q38-B)") (class "Default")
      (node (ref "Q38") (pin "1") (pinfunction "B_1") (pintype "passive"))
      (node (ref "R83") (pin "2") (pinfunction "2_2") (pintype "passive"))
    )
    (net (code "201") (name "Net-(Q38-C)") (class "Default")
      (node (ref "Q38") (pin "3") (pinfunction "C_3") (pintype "passive"))
      (node (ref "R82") (pin "1") (pinfunction "1_1") (pintype "passive"))
    )
    (net (code "202") (name "Net-(Q39-B)") (class "Default")
      (node (ref "Q39") (pin "1") (pinfunction "B_1") (pintype "passive"))
      (node (ref "R81") (pin "1") (pinfunction "1_1") (pintype "passive"))
      (node (ref "R82") (pin "2") (pinfunction "2_2") (pintype "passive"))
    )
    (net (code "203") (name "Net-(Q39-C)") (class "Default")
      (node (ref "Q39") (pin "3") (pinfunction "C_3") (pintype "passive"))
      (node (ref "R61") (pin "2") (pinfunction "2_2") (pintype "passive"))
      (node (ref "R62") (pin "2") (pinfunction "2_2") (pintype "passive"))
    )
    (net (code "204") (name "Net-(U41-Q7S)") (class "Default")
      (node (ref "TP1") (pin "1") (pinfunction "1_1") (pintype "passive"))
      (node (ref "U41") (pin "9") (pinfunction "Q7S_9") (pintype "passive"))
      (node (ref "U42") (pin "14") (pinfunction "DS_14") (pintype "passive"))
    )
    (net (code "205") (name "Net-(U42-Q7S)") (class "Default")
      (node (ref "TP2") (pin "1") (pinfunction "1_1") (pintype "passive"))
      (node (ref "U42") (pin "9") (pinfunction "Q7S_9") (pintype "passive"))
      (node (ref "U44") (pin "14") (pinfunction "DS_14") (pintype "passive"))
    )
    (net (code "206") (name "Net-(U44-Q7S)") (class "Default")
      (node (ref "TP3") (pin "1") (pinfunction "1_1") (pintype "passive"))
      (node (ref "U44") (pin "9") (pinfunction "Q7S_9") (pintype "passive"))
      (node (ref "U48") (pin "14") (pinfunction "DS_14") (pintype "passive"))
    )
    (net (code "207") (name "Net-(U48-Q7S)") (class "Default")
      (node (ref "TP4") (pin "1") (pinfunction "1_1") (pintype "passive"))
      (node (ref "U48") (pin "9") (pinfunction "Q7S_9") (pintype "passive"))
      (node (ref "U49") (pin "14") (pinfunction "DS_14") (pintype "passive"))
    )
    (net (code "208") (name "Net-(U49-Q7S)") (class "Default")
      (node (ref "TP5") (pin "1") (pinfunction "1_1") (pintype "passive"))
      (node (ref "U49") (pin "9") (pinfunction "Q7S_9") (pintype "passive"))
      (node (ref "U50") (pin "14") (pinfunction "DS_14") (pintype "passive"))
    )
    (net (code "209") (name "Net-(U50-Q7S)") (class "Default")
      (node (ref "TP6") (pin "1") (pinfunction "1_1") (pintype "passive"))
      (node (ref "U50") (pin "9") (pinfunction "Q7S_9") (pintype "passive"))
      (node (ref "U51") (pin "14") (pinfunction "DS_14") (pintype "passive"))
    )
    (net (code "210") (name "Net-(U51-Q7S)") (class "Default")
      (node (ref "TP7") (pin "1") (pinfunction "1_1") (pintype "passive"))
      (node (ref "U51") (pin "9") (pinfunction "Q7S_9") (pintype "passive"))
      (node (ref "U52") (pin "14") (pinfunction "DS_14") (pintype "passive"))
    )
    (net (code "211") (name "Net-(U52-Q7S)") (class "Default")
      (node (ref "TP8") (pin "1") (pinfunction "1_1") (pintype "passive"))
      (node (ref "U52") (pin "9") (pinfunction "Q7S_9") (pintype "passive"))
      (node (ref "U53") (pin "14") (pinfunction "DS_14") (pintype "passive"))
    )
    (net (code "212") (name "PGND") (class "Default")
      (node (ref "CN4") (pin "1") (pinfunction "1_1") (pintype "passive"))
      (node (ref "CN4") (pin "2") (pinfunction "2_2") (pintype "passive"))
      (node (ref "D10") (pin "2") (pinfunction "A_2") (pintype "passive"))
      (node (ref "D11") (pin "2") (pinfunction "A_2") (pintype "passive"))
      (node (ref "D12") (pin "2") (pinfunction "A_2") (pintype "passive"))
      (node (ref "D13") (pin "2") (pinfunction "A_2") (pintype "passive"))
      (node (ref "D14") (pin "2") (pinfunction "A_2") (pintype "passive"))
      (node (ref "D15") (pin "2") (pinfunction "A_2") (pintype "passive"))
      (node (ref "D6") (pin "2") (pinfunction "A_2") (pintype "passive"))
      (node (ref "D8") (pin "2") (pinfunction "A_2") (pintype "passive"))
      (node (ref "D9") (pin "2") (pinfunction "A_2") (pintype "passive"))
      (node (ref "H4") (pin "1") (pinfunction "1_1") (pintype "passive"))
      (node (ref "Q1") (pin "2") (pinfunction "E_2") (pintype "passive"))
      (node (ref "Q26") (pin "2") (pinfunction "E_2") (pintype "passive"))
      (node (ref "Q28") (pin "2") (pinfunction "E_2") (pintype "passive"))
      (node (ref "Q30") (pin "2") (pinfunction "E_2") (pintype "passive"))
      (node (ref "Q32") (pin "2") (pinfunction "E_2") (pintype "passive"))
      (node (ref "Q34") (pin "2") (pinfunction "E_2") (pintype "passive"))
      (node (ref "Q36") (pin "2") (pinfunction "E_2") (pintype "passive"))
      (node (ref "Q38") (pin "2") (pinfunction "E_2") (pintype "passive"))
      (node (ref "U40") (pin "21") (pinfunction "EP_21") (pintype "passive"))
      (node (ref "U40") (pin "8") (pinfunction "E_8") (pintype "passive"))
      (node (ref "U45") (pin "21") (pinfunction "EP_21") (pintype "passive"))
      (node (ref "U45") (pin "8") (pinfunction "E_8") (pintype "passive"))
      (node (ref "U46") (pin "21") (pinfunction "EP_21") (pintype "passive"))
      (node (ref "U46") (pin "8") (pinfunction "E_8") (pintype "passive"))
      (node (ref "U54") (pin "21") (pinfunction "EP_21") (pintype "passive"))
      (node (ref "U54") (pin "8") (pinfunction "E_8") (pintype "passive"))
      (node (ref "U55") (pin "21") (pinfunction "EP_21") (pintype "passive"))
      (node (ref "U55") (pin "8") (pinfunction "E_8") (pintype "passive"))
      (node (ref "U56") (pin "21") (pinfunction "EP_21") (pintype "passive"))
      (node (ref "U56") (pin "8") (pinfunction "E_8") (pintype "passive"))
      (node (ref "U57") (pin "21") (pinfunction "EP_21") (pintype "passive"))
      (node (ref "U57") (pin "8") (pinfunction "E_8") (pintype "passive"))
      (node (ref "U58") (pin "21") (pinfunction "EP_21") (pintype "passive"))
      (node (ref "U58") (pin "8") (pinfunction "E_8") (pintype "passive"))
      (node (ref "U59") (pin "21") (pinfunction "EP_21") (pintype "passive"))
      (node (ref "U59") (pin "8") (pinfunction "E_8") (pintype "passive"))
    )
    (net (code "213") (name "unconnected-(H4-Pad5)") (class "Default")
      (node (ref "H4") (pin "5") (pinfunction "5_5") (pintype "passive+no_connect"))
    )
    (net (code "214") (name "unconnected-(H4-Pad8)") (class "Default")
      (node (ref "H4") (pin "8") (pinfunction "8_8") (pintype "passive+no_connect"))
    )
    (net (code "215") (name "unconnected-(U40-NC-Pad7)") (class "Default")
      (node (ref "U40") (pin "7") (pinfunction "NC_7") (pintype "passive+no_connect"))
    )
    (net (code "216") (name "unconnected-(U40-NC-Pad18)") (class "Default")
      (node (ref "U40") (pin "18") (pinfunction "NC_18") (pintype "passive+no_connect"))
    )
    (net (code "217") (name "unconnected-(U45-NC-Pad7)") (class "Default")
      (node (ref "U45") (pin "7") (pinfunction "NC_7") (pintype "passive+no_connect"))
    )
    (net (code "218") (name "unconnected-(U45-NC-Pad18)") (class "Default")
      (node (ref "U45") (pin "18") (pinfunction "NC_18") (pintype "passive+no_connect"))
    )
    (net (code "219") (name "unconnected-(U46-NC-Pad7)") (class "Default")
      (node (ref "U46") (pin "7") (pinfunction "NC_7") (pintype "passive+no_connect"))
    )
    (net (code "220") (name "unconnected-(U46-NC-Pad18)") (class "Default")
      (node (ref "U46") (pin "18") (pinfunction "NC_18") (pintype "passive+no_connect"))
    )
    (net (code "221") (name "unconnected-(U53-Q6-Pad6)") (class "Default")
      (node (ref "U53") (pin "6") (pinfunction "Q6_6") (pintype "passive+no_connect"))
    )
    (net (code "222") (name "unconnected-(U53-Q7-Pad7)") (class "Default")
      (node (ref "U53") (pin "7") (pinfunction "Q7_7") (pintype "passive+no_connect"))
    )
    (net (code "223") (name "unconnected-(U53-Q7S-Pad9)") (class "Default")
      (node (ref "U53") (pin "9") (pinfunction "Q7S_9") (pintype "passive+no_connect"))
    )
    (net (code "224") (name "unconnected-(U54-NC-Pad7)") (class "Default")
      (node (ref "U54") (pin "7") (pinfunction "NC_7") (pintype "passive+no_connect"))
    )
    (net (code "225") (name "unconnected-(U54-NC-Pad18)") (class "Default")
      (node (ref "U54") (pin "18") (pinfunction "NC_18") (pintype "passive+no_connect"))
    )
    (net (code "226") (name "unconnected-(U55-NC-Pad7)") (class "Default")
      (node (ref "U55") (pin "7") (pinfunction "NC_7") (pintype "passive+no_connect"))
    )
    (net (code "227") (name "unconnected-(U55-NC-Pad18)") (class "Default")
      (node (ref "U55") (pin "18") (pinfunction "NC_18") (pintype "passive+no_connect"))
    )
    (net (code "228") (name "unconnected-(U56-NC-Pad7)") (class "Default")
      (node (ref "U56") (pin "7") (pinfunction "NC_7") (pintype "passive+no_connect"))
    )
    (net (code "229") (name "unconnected-(U56-NC-Pad18)") (class "Default")
      (node (ref "U56") (pin "18") (pinfunction "NC_18") (pintype "passive+no_connect"))
    )
    (net (code "230") (name "unconnected-(U57-NC-Pad7)") (class "Default")
      (node (ref "U57") (pin "7") (pinfunction "NC_7") (pintype "passive+no_connect"))
    )
    (net (code "231") (name "unconnected-(U57-NC-Pad18)") (class "Default")
      (node (ref "U57") (pin "18") (pinfunction "NC_18") (pintype "passive+no_connect"))
    )
    (net (code "232") (name "unconnected-(U58-NC-Pad7)") (class "Default")
      (node (ref "U58") (pin "7") (pinfunction "NC_7") (pintype "passive+no_connect"))
    )
    (net (code "233") (name "unconnected-(U58-NC-Pad18)") (class "Default")
      (node (ref "U58") (pin "18") (pinfunction "NC_18") (pintype "passive+no_connect"))
    )
    (net (code "234") (name "unconnected-(U59-1B-Pad19)") (class "Default")
      (node (ref "U59") (pin "19") (pinfunction "1B_19") (pintype "passive+no_connect"))
    )
    (net (code "235") (name "unconnected-(U59-1C-Pad17)") (class "Default")
      (node (ref "U59") (pin "17") (pinfunction "1C_17") (pintype "passive+no_connect"))
    )
    (net (code "236") (name "unconnected-(U59-2B-Pad20)") (class "Default")
      (node (ref "U59") (pin "20") (pinfunction "2B_20") (pintype "passive+no_connect"))
    )
    (net (code "237") (name "unconnected-(U59-2C-Pad16)") (class "Default")
      (node (ref "U59") (pin "16") (pinfunction "2C_16") (pintype "passive+no_connect"))
    )
    (net (code "238") (name "unconnected-(U59-NC-Pad7)") (class "Default")
      (node (ref "U59") (pin "7") (pinfunction "NC_7") (pintype "passive+no_connect"))
    )
    (net (code "239") (name "unconnected-(U59-NC-Pad18)") (class "Default")
      (node (ref "U59") (pin "18") (pinfunction "NC_18") (pintype "passive+no_connect"))
    )
  )
)
